# RowDriver4.net
KiCad netlist of a schematic drawn in EAGLE
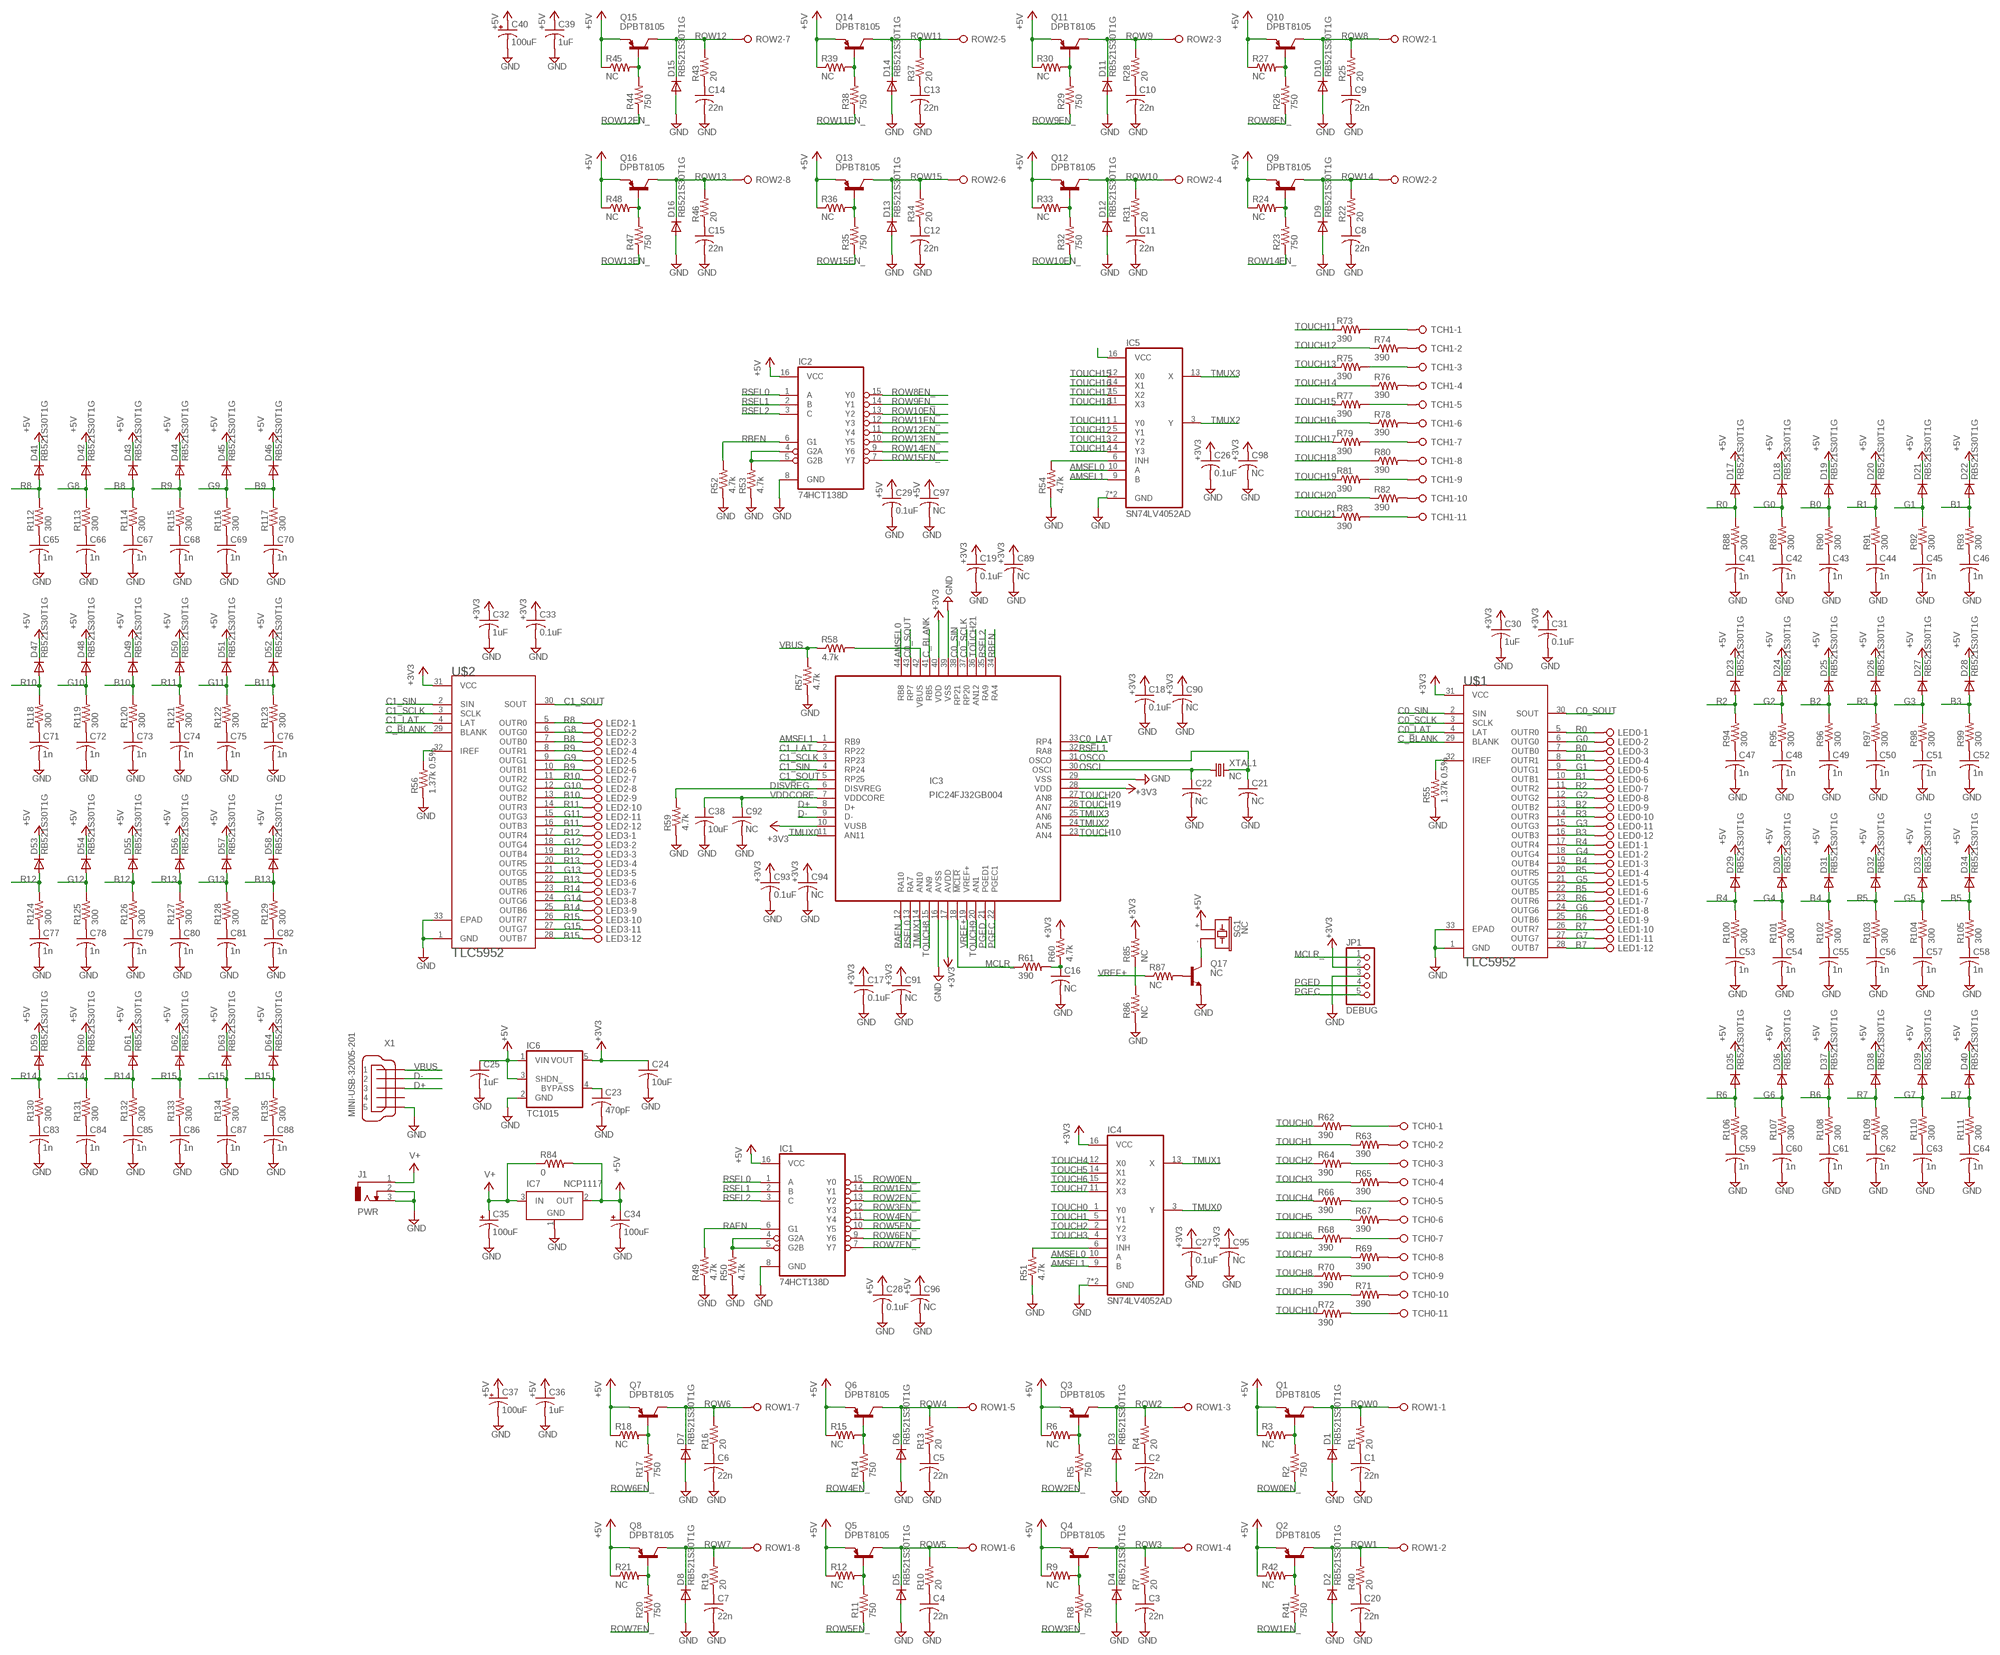
[diagram p0: schematic, sheet 1]

(export (version "E")
  (design (tool "Eeschema 10.0.6"))
  (components
    (comp (ref "C1")
      (value "22n")
      (footprint "eagle-import:C0603")
      (libsource (lib "eagle-import") (part "resistor_C-USC0603"))
    )
    (comp (ref "C2")
      (value "22n")
      (footprint "eagle-import:C0603")
      (libsource (lib "eagle-import") (part "resistor_C-USC0603"))
    )
    (comp (ref "C3")
      (value "22n")
      (footprint "eagle-import:C0603")
      (libsource (lib "eagle-import") (part "resistor_C-USC0603"))
    )
    (comp (ref "C4")
      (value "22n")
      (footprint "eagle-import:C0603")
      (libsource (lib "eagle-import") (part "resistor_C-USC0603"))
    )
    (comp (ref "C5")
      (value "22n")
      (footprint "eagle-import:C0603")
      (libsource (lib "eagle-import") (part "resistor_C-USC0603"))
    )
    (comp (ref "C6")
      (value "22n")
      (footprint "eagle-import:C0603")
      (libsource (lib "eagle-import") (part "resistor_C-USC0603"))
    )
    (comp (ref "C7")
      (value "22n")
      (footprint "eagle-import:C0603")
      (libsource (lib "eagle-import") (part "resistor_C-USC0603"))
    )
    (comp (ref "C8")
      (value "22n")
      (footprint "eagle-import:C0603")
      (libsource (lib "eagle-import") (part "resistor_C-USC0603"))
    )
    (comp (ref "C9")
      (value "22n")
      (footprint "eagle-import:C0603")
      (libsource (lib "eagle-import") (part "resistor_C-USC0603"))
    )
    (comp (ref "C10")
      (value "22n")
      (footprint "eagle-import:C0603")
      (libsource (lib "eagle-import") (part "resistor_C-USC0603"))
    )
    (comp (ref "C11")
      (value "22n")
      (footprint "eagle-import:C0603")
      (libsource (lib "eagle-import") (part "resistor_C-USC0603"))
    )
    (comp (ref "C12")
      (value "22n")
      (footprint "eagle-import:C0603")
      (libsource (lib "eagle-import") (part "resistor_C-USC0603"))
    )
    (comp (ref "C13")
      (value "22n")
      (footprint "eagle-import:C0603")
      (libsource (lib "eagle-import") (part "resistor_C-USC0603"))
    )
    (comp (ref "C14")
      (value "22n")
      (footprint "eagle-import:C0603")
      (libsource (lib "eagle-import") (part "resistor_C-USC0603"))
    )
    (comp (ref "C15")
      (value "22n")
      (footprint "eagle-import:C0603")
      (libsource (lib "eagle-import") (part "resistor_C-USC0603"))
    )
    (comp (ref "C16")
      (value "NC")
      (footprint "eagle-import:C0805")
      (libsource (lib "eagle-import") (part "C-USC0805"))
    )
    (comp (ref "C17")
      (value "0.1uF")
      (footprint "eagle-import:C0805")
      (libsource (lib "eagle-import") (part "C-USC0805"))
    )
    (comp (ref "C18")
      (value "0.1uF")
      (footprint "eagle-import:C0805")
      (libsource (lib "eagle-import") (part "C-USC0805"))
    )
    (comp (ref "C19")
      (value "0.1uF")
      (footprint "eagle-import:C0805")
      (libsource (lib "eagle-import") (part "C-USC0805"))
    )
    (comp (ref "C20")
      (value "22n")
      (footprint "eagle-import:C0603")
      (libsource (lib "eagle-import") (part "resistor_C-USC0603"))
    )
    (comp (ref "C21")
      (value "NC")
      (footprint "eagle-import:C0805")
      (libsource (lib "eagle-import") (part "C-USC0805"))
    )
    (comp (ref "C22")
      (value "NC")
      (footprint "eagle-import:C0805")
      (libsource (lib "eagle-import") (part "C-USC0805"))
    )
    (comp (ref "C23")
      (value "470pF")
      (footprint "eagle-import:C0805")
      (libsource (lib "eagle-import") (part "C-USC0805"))
    )
    (comp (ref "C24")
      (value "10uF")
      (footprint "eagle-import:C1206K")
      (libsource (lib "eagle-import") (part "C-USC1206K"))
    )
    (comp (ref "C25")
      (value "1uF")
      (footprint "eagle-import:C0805")
      (libsource (lib "eagle-import") (part "C-USC0805"))
    )
    (comp (ref "C26")
      (value "0.1uF")
      (footprint "eagle-import:C0805")
      (libsource (lib "eagle-import") (part "C-USC0805"))
    )
    (comp (ref "C27")
      (value "0.1uF")
      (footprint "eagle-import:C0805")
      (libsource (lib "eagle-import") (part "C-USC0805"))
    )
    (comp (ref "C28")
      (value "0.1uF")
      (footprint "eagle-import:C0805")
      (libsource (lib "eagle-import") (part "C-USC0805"))
    )
    (comp (ref "C29")
      (value "0.1uF")
      (footprint "eagle-import:C0805")
      (libsource (lib "eagle-import") (part "C-USC0805"))
    )
    (comp (ref "C30")
      (value "1uF")
      (footprint "eagle-import:C0805")
      (libsource (lib "eagle-import") (part "C-USC0805"))
    )
    (comp (ref "C31")
      (value "0.1uF")
      (footprint "eagle-import:C0805")
      (libsource (lib "eagle-import") (part "C-USC0805"))
    )
    (comp (ref "C32")
      (value "1uF")
      (footprint "eagle-import:C0805")
      (libsource (lib "eagle-import") (part "C-USC0805"))
    )
    (comp (ref "C33")
      (value "0.1uF")
      (footprint "eagle-import:C0805")
      (libsource (lib "eagle-import") (part "C-USC0805"))
    )
    (comp (ref "C34")
      (value "100uF")
      (footprint "eagle-import:PANASONIC_D")
      (libsource (lib "eagle-import") (part "CPOL-USD"))
    )
    (comp (ref "C35")
      (value "100uF")
      (footprint "eagle-import:PANASONIC_D")
      (libsource (lib "eagle-import") (part "CPOL-USD"))
    )
    (comp (ref "C36")
      (value "1uF")
      (footprint "eagle-import:C0805")
      (libsource (lib "eagle-import") (part "C-USC0805"))
    )
    (comp (ref "C37")
      (value "100uF")
      (footprint "eagle-import:PANASONIC_D")
      (libsource (lib "eagle-import") (part "CPOL-USD"))
    )
    (comp (ref "C38")
      (value "10uF")
      (footprint "eagle-import:C1206K")
      (libsource (lib "eagle-import") (part "C-USC1206K"))
    )
    (comp (ref "C39")
      (value "1uF")
      (footprint "eagle-import:C0805")
      (libsource (lib "eagle-import") (part "C-USC0805"))
    )
    (comp (ref "C40")
      (value "100uF")
      (footprint "eagle-import:PANASONIC_D")
      (libsource (lib "eagle-import") (part "CPOL-USD"))
    )
    (comp (ref "C41")
      (value "1n")
      (footprint "eagle-import:C0805")
      (libsource (lib "eagle-import") (part "resistor_C-USC0805"))
    )
    (comp (ref "C42")
      (value "1n")
      (footprint "eagle-import:C0805")
      (libsource (lib "eagle-import") (part "resistor_C-USC0805"))
    )
    (comp (ref "C43")
      (value "1n")
      (footprint "eagle-import:C0805")
      (libsource (lib "eagle-import") (part "resistor_C-USC0805"))
    )
    (comp (ref "C44")
      (value "1n")
      (footprint "eagle-import:C0805")
      (libsource (lib "eagle-import") (part "resistor_C-USC0805"))
    )
    (comp (ref "C45")
      (value "1n")
      (footprint "eagle-import:C0805")
      (libsource (lib "eagle-import") (part "resistor_C-USC0805"))
    )
    (comp (ref "C46")
      (value "1n")
      (footprint "eagle-import:C0805")
      (libsource (lib "eagle-import") (part "resistor_C-USC0805"))
    )
    (comp (ref "C47")
      (value "1n")
      (footprint "eagle-import:C0805")
      (libsource (lib "eagle-import") (part "resistor_C-USC0805"))
    )
    (comp (ref "C48")
      (value "1n")
      (footprint "eagle-import:C0805")
      (libsource (lib "eagle-import") (part "resistor_C-USC0805"))
    )
    (comp (ref "C49")
      (value "1n")
      (footprint "eagle-import:C0805")
      (libsource (lib "eagle-import") (part "resistor_C-USC0805"))
    )
    (comp (ref "C50")
      (value "1n")
      (footprint "eagle-import:C0805")
      (libsource (lib "eagle-import") (part "resistor_C-USC0805"))
    )
    (comp (ref "C51")
      (value "1n")
      (footprint "eagle-import:C0805")
      (libsource (lib "eagle-import") (part "resistor_C-USC0805"))
    )
    (comp (ref "C52")
      (value "1n")
      (footprint "eagle-import:C0805")
      (libsource (lib "eagle-import") (part "resistor_C-USC0805"))
    )
    (comp (ref "C53")
      (value "1n")
      (footprint "eagle-import:C0805")
      (libsource (lib "eagle-import") (part "resistor_C-USC0805"))
    )
    (comp (ref "C54")
      (value "1n")
      (footprint "eagle-import:C0805")
      (libsource (lib "eagle-import") (part "resistor_C-USC0805"))
    )
    (comp (ref "C55")
      (value "1n")
      (footprint "eagle-import:C0805")
      (libsource (lib "eagle-import") (part "resistor_C-USC0805"))
    )
    (comp (ref "C56")
      (value "1n")
      (footprint "eagle-import:C0805")
      (libsource (lib "eagle-import") (part "resistor_C-USC0805"))
    )
    (comp (ref "C57")
      (value "1n")
      (footprint "eagle-import:C0805")
      (libsource (lib "eagle-import") (part "resistor_C-USC0805"))
    )
    (comp (ref "C58")
      (value "1n")
      (footprint "eagle-import:C0805")
      (libsource (lib "eagle-import") (part "resistor_C-USC0805"))
    )
    (comp (ref "C59")
      (value "1n")
      (footprint "eagle-import:C0805")
      (libsource (lib "eagle-import") (part "resistor_C-USC0805"))
    )
    (comp (ref "C60")
      (value "1n")
      (footprint "eagle-import:C0805")
      (libsource (lib "eagle-import") (part "resistor_C-USC0805"))
    )
    (comp (ref "C61")
      (value "1n")
      (footprint "eagle-import:C0805")
      (libsource (lib "eagle-import") (part "resistor_C-USC0805"))
    )
    (comp (ref "C62")
      (value "1n")
      (footprint "eagle-import:C0805")
      (libsource (lib "eagle-import") (part "resistor_C-USC0805"))
    )
    (comp (ref "C63")
      (value "1n")
      (footprint "eagle-import:C0805")
      (libsource (lib "eagle-import") (part "resistor_C-USC0805"))
    )
    (comp (ref "C64")
      (value "1n")
      (footprint "eagle-import:C0805")
      (libsource (lib "eagle-import") (part "resistor_C-USC0805"))
    )
    (comp (ref "C65")
      (value "1n")
      (footprint "eagle-import:C0805")
      (libsource (lib "eagle-import") (part "resistor_C-USC0805"))
    )
    (comp (ref "C66")
      (value "1n")
      (footprint "eagle-import:C0805")
      (libsource (lib "eagle-import") (part "resistor_C-USC0805"))
    )
    (comp (ref "C67")
      (value "1n")
      (footprint "eagle-import:C0805")
      (libsource (lib "eagle-import") (part "resistor_C-USC0805"))
    )
    (comp (ref "C68")
      (value "1n")
      (footprint "eagle-import:C0805")
      (libsource (lib "eagle-import") (part "resistor_C-USC0805"))
    )
    (comp (ref "C69")
      (value "1n")
      (footprint "eagle-import:C0805")
      (libsource (lib "eagle-import") (part "resistor_C-USC0805"))
    )
    (comp (ref "C70")
      (value "1n")
      (footprint "eagle-import:C0805")
      (libsource (lib "eagle-import") (part "resistor_C-USC0805"))
    )
    (comp (ref "C71")
      (value "1n")
      (footprint "eagle-import:C0805")
      (libsource (lib "eagle-import") (part "resistor_C-USC0805"))
    )
    (comp (ref "C72")
      (value "1n")
      (footprint "eagle-import:C0805")
      (libsource (lib "eagle-import") (part "resistor_C-USC0805"))
    )
    (comp (ref "C73")
      (value "1n")
      (footprint "eagle-import:C0805")
      (libsource (lib "eagle-import") (part "resistor_C-USC0805"))
    )
    (comp (ref "C74")
      (value "1n")
      (footprint "eagle-import:C0805")
      (libsource (lib "eagle-import") (part "resistor_C-USC0805"))
    )
    (comp (ref "C75")
      (value "1n")
      (footprint "eagle-import:C0805")
      (libsource (lib "eagle-import") (part "resistor_C-USC0805"))
    )
    (comp (ref "C76")
      (value "1n")
      (footprint "eagle-import:C0805")
      (libsource (lib "eagle-import") (part "resistor_C-USC0805"))
    )
    (comp (ref "C77")
      (value "1n")
      (footprint "eagle-import:C0805")
      (libsource (lib "eagle-import") (part "resistor_C-USC0805"))
    )
    (comp (ref "C78")
      (value "1n")
      (footprint "eagle-import:C0805")
      (libsource (lib "eagle-import") (part "resistor_C-USC0805"))
    )
    (comp (ref "C79")
      (value "1n")
      (footprint "eagle-import:C0805")
      (libsource (lib "eagle-import") (part "resistor_C-USC0805"))
    )
    (comp (ref "C80")
      (value "1n")
      (footprint "eagle-import:C0805")
      (libsource (lib "eagle-import") (part "resistor_C-USC0805"))
    )
    (comp (ref "C81")
      (value "1n")
      (footprint "eagle-import:C0805")
      (libsource (lib "eagle-import") (part "resistor_C-USC0805"))
    )
    (comp (ref "C82")
      (value "1n")
      (footprint "eagle-import:C0805")
      (libsource (lib "eagle-import") (part "resistor_C-USC0805"))
    )
    (comp (ref "C83")
      (value "1n")
      (footprint "eagle-import:C0805")
      (libsource (lib "eagle-import") (part "resistor_C-USC0805"))
    )
    (comp (ref "C84")
      (value "1n")
      (footprint "eagle-import:C0805")
      (libsource (lib "eagle-import") (part "resistor_C-USC0805"))
    )
    (comp (ref "C85")
      (value "1n")
      (footprint "eagle-import:C0805")
      (libsource (lib "eagle-import") (part "resistor_C-USC0805"))
    )
    (comp (ref "C86")
      (value "1n")
      (footprint "eagle-import:C0805")
      (libsource (lib "eagle-import") (part "resistor_C-USC0805"))
    )
    (comp (ref "C87")
      (value "1n")
      (footprint "eagle-import:C0805")
      (libsource (lib "eagle-import") (part "resistor_C-USC0805"))
    )
    (comp (ref "C88")
      (value "1n")
      (footprint "eagle-import:C0805")
      (libsource (lib "eagle-import") (part "resistor_C-USC0805"))
    )
    (comp (ref "C89")
      (value "NC")
      (footprint "eagle-import:C0805")
      (libsource (lib "eagle-import") (part "C-USC0805"))
    )
    (comp (ref "C90")
      (value "NC")
      (footprint "eagle-import:C0805")
      (libsource (lib "eagle-import") (part "C-USC0805"))
    )
    (comp (ref "C91")
      (value "NC")
      (footprint "eagle-import:C0805")
      (libsource (lib "eagle-import") (part "C-USC0805"))
    )
    (comp (ref "C92")
      (value "NC")
      (footprint "eagle-import:C0805")
      (libsource (lib "eagle-import") (part "C-USC0805"))
    )
    (comp (ref "C93")
      (value "0.1uF")
      (footprint "eagle-import:C0805")
      (libsource (lib "eagle-import") (part "C-USC0805"))
    )
    (comp (ref "C94")
      (value "NC")
      (footprint "eagle-import:C0805")
      (libsource (lib "eagle-import") (part "C-USC0805"))
    )
    (comp (ref "C95")
      (value "NC")
      (footprint "eagle-import:C0805")
      (libsource (lib "eagle-import") (part "C-USC0805"))
    )
    (comp (ref "C96")
      (value "NC")
      (footprint "eagle-import:C0805")
      (libsource (lib "eagle-import") (part "C-USC0805"))
    )
    (comp (ref "C97")
      (value "NC")
      (footprint "eagle-import:C0805")
      (libsource (lib "eagle-import") (part "C-USC0805"))
    )
    (comp (ref "C98")
      (value "NC")
      (footprint "eagle-import:C0805")
      (libsource (lib "eagle-import") (part "C-USC0805"))
    )
    (comp (ref "D1")
      (value "RB521S30T1G")
      (footprint "eagle-import:SOD523")
      (libsource (lib "eagle-import") (part "DIODE-SOD523"))
    )
    (comp (ref "D2")
      (value "RB521S30T1G")
      (footprint "eagle-import:SOD523")
      (libsource (lib "eagle-import") (part "DIODE-SOD523"))
    )
    (comp (ref "D3")
      (value "RB521S30T1G")
      (footprint "eagle-import:SOD523")
      (libsource (lib "eagle-import") (part "DIODE-SOD523"))
    )
    (comp (ref "D4")
      (value "RB521S30T1G")
      (footprint "eagle-import:SOD523")
      (libsource (lib "eagle-import") (part "DIODE-SOD523"))
    )
    (comp (ref "D5")
      (value "RB521S30T1G")
      (footprint "eagle-import:SOD523")
      (libsource (lib "eagle-import") (part "DIODE-SOD523"))
    )
    (comp (ref "D6")
      (value "RB521S30T1G")
      (footprint "eagle-import:SOD523")
      (libsource (lib "eagle-import") (part "DIODE-SOD523"))
    )
    (comp (ref "D7")
      (value "RB521S30T1G")
      (footprint "eagle-import:SOD523")
      (libsource (lib "eagle-import") (part "DIODE-SOD523"))
    )
    (comp (ref "D8")
      (value "RB521S30T1G")
      (footprint "eagle-import:SOD523")
      (libsource (lib "eagle-import") (part "DIODE-SOD523"))
    )
    (comp (ref "D9")
      (value "RB521S30T1G")
      (footprint "eagle-import:SOD523")
      (libsource (lib "eagle-import") (part "DIODE-SOD523"))
    )
    (comp (ref "D10")
      (value "RB521S30T1G")
      (footprint "eagle-import:SOD523")
      (libsource (lib "eagle-import") (part "DIODE-SOD523"))
    )
    (comp (ref "D11")
      (value "RB521S30T1G")
      (footprint "eagle-import:SOD523")
      (libsource (lib "eagle-import") (part "DIODE-SOD523"))
    )
    (comp (ref "D12")
      (value "RB521S30T1G")
      (footprint "eagle-import:SOD523")
      (libsource (lib "eagle-import") (part "DIODE-SOD523"))
    )
    (comp (ref "D13")
      (value "RB521S30T1G")
      (footprint "eagle-import:SOD523")
      (libsource (lib "eagle-import") (part "DIODE-SOD523"))
    )
    (comp (ref "D14")
      (value "RB521S30T1G")
      (footprint "eagle-import:SOD523")
      (libsource (lib "eagle-import") (part "DIODE-SOD523"))
    )
    (comp (ref "D15")
      (value "RB521S30T1G")
      (footprint "eagle-import:SOD523")
      (libsource (lib "eagle-import") (part "DIODE-SOD523"))
    )
    (comp (ref "D16")
      (value "RB521S30T1G")
      (footprint "eagle-import:SOD523")
      (libsource (lib "eagle-import") (part "DIODE-SOD523"))
    )
    (comp (ref "D17")
      (value "RB521S30T1G")
      (footprint "eagle-import:SOD523")
      (libsource (lib "eagle-import") (part "DIODE-SOD523"))
    )
    (comp (ref "D18")
      (value "RB521S30T1G")
      (footprint "eagle-import:SOD523")
      (libsource (lib "eagle-import") (part "DIODE-SOD523"))
    )
    (comp (ref "D19")
      (value "RB521S30T1G")
      (footprint "eagle-import:SOD523")
      (libsource (lib "eagle-import") (part "DIODE-SOD523"))
    )
    (comp (ref "D20")
      (value "RB521S30T1G")
      (footprint "eagle-import:SOD523")
      (libsource (lib "eagle-import") (part "DIODE-SOD523"))
    )
    (comp (ref "D21")
      (value "RB521S30T1G")
      (footprint "eagle-import:SOD523")
      (libsource (lib "eagle-import") (part "DIODE-SOD523"))
    )
    (comp (ref "D22")
      (value "RB521S30T1G")
      (footprint "eagle-import:SOD523")
      (libsource (lib "eagle-import") (part "DIODE-SOD523"))
    )
    (comp (ref "D23")
      (value "RB521S30T1G")
      (footprint "eagle-import:SOD523")
      (libsource (lib "eagle-import") (part "DIODE-SOD523"))
    )
    (comp (ref "D24")
      (value "RB521S30T1G")
      (footprint "eagle-import:SOD523")
      (libsource (lib "eagle-import") (part "DIODE-SOD523"))
    )
    (comp (ref "D25")
      (value "RB521S30T1G")
      (footprint "eagle-import:SOD523")
      (libsource (lib "eagle-import") (part "DIODE-SOD523"))
    )
    (comp (ref "D26")
      (value "RB521S30T1G")
      (footprint "eagle-import:SOD523")
      (libsource (lib "eagle-import") (part "DIODE-SOD523"))
    )
    (comp (ref "D27")
      (value "RB521S30T1G")
      (footprint "eagle-import:SOD523")
      (libsource (lib "eagle-import") (part "DIODE-SOD523"))
    )
    (comp (ref "D28")
      (value "RB521S30T1G")
      (footprint "eagle-import:SOD523")
      (libsource (lib "eagle-import") (part "DIODE-SOD523"))
    )
    (comp (ref "D29")
      (value "RB521S30T1G")
      (footprint "eagle-import:SOD523")
      (libsource (lib "eagle-import") (part "DIODE-SOD523"))
    )
    (comp (ref "D30")
      (value "RB521S30T1G")
      (footprint "eagle-import:SOD523")
      (libsource (lib "eagle-import") (part "DIODE-SOD523"))
    )
    (comp (ref "D31")
      (value "RB521S30T1G")
      (footprint "eagle-import:SOD523")
      (libsource (lib "eagle-import") (part "DIODE-SOD523"))
    )
    (comp (ref "D32")
      (value "RB521S30T1G")
      (footprint "eagle-import:SOD523")
      (libsource (lib "eagle-import") (part "DIODE-SOD523"))
    )
    (comp (ref "D33")
      (value "RB521S30T1G")
      (footprint "eagle-import:SOD523")
      (libsource (lib "eagle-import") (part "DIODE-SOD523"))
    )
    (comp (ref "D34")
      (value "RB521S30T1G")
      (footprint "eagle-import:SOD523")
      (libsource (lib "eagle-import") (part "DIODE-SOD523"))
    )
    (comp (ref "D35")
      (value "RB521S30T1G")
      (footprint "eagle-import:SOD523")
      (libsource (lib "eagle-import") (part "DIODE-SOD523"))
    )
    (comp (ref "D36")
      (value "RB521S30T1G")
      (footprint "eagle-import:SOD523")
      (libsource (lib "eagle-import") (part "DIODE-SOD523"))
    )
    (comp (ref "D37")
      (value "RB521S30T1G")
      (footprint "eagle-import:SOD523")
      (libsource (lib "eagle-import") (part "DIODE-SOD523"))
    )
    (comp (ref "D38")
      (value "RB521S30T1G")
      (footprint "eagle-import:SOD523")
      (libsource (lib "eagle-import") (part "DIODE-SOD523"))
    )
    (comp (ref "D39")
      (value "RB521S30T1G")
      (footprint "eagle-import:SOD523")
      (libsource (lib "eagle-import") (part "DIODE-SOD523"))
    )
    (comp (ref "D40")
      (value "RB521S30T1G")
      (footprint "eagle-import:SOD523")
      (libsource (lib "eagle-import") (part "DIODE-SOD523"))
    )
    (comp (ref "D41")
      (value "RB521S30T1G")
      (footprint "eagle-import:SOD523")
      (libsource (lib "eagle-import") (part "DIODE-SOD523"))
    )
    (comp (ref "D42")
      (value "RB521S30T1G")
      (footprint "eagle-import:SOD523")
      (libsource (lib "eagle-import") (part "DIODE-SOD523"))
    )
    (comp (ref "D43")
      (value "RB521S30T1G")
      (footprint "eagle-import:SOD523")
      (libsource (lib "eagle-import") (part "DIODE-SOD523"))
    )
    (comp (ref "D44")
      (value "RB521S30T1G")
      (footprint "eagle-import:SOD523")
      (libsource (lib "eagle-import") (part "DIODE-SOD523"))
    )
    (comp (ref "D45")
      (value "RB521S30T1G")
      (footprint "eagle-import:SOD523")
      (libsource (lib "eagle-import") (part "DIODE-SOD523"))
    )
    (comp (ref "D46")
      (value "RB521S30T1G")
      (footprint "eagle-import:SOD523")
      (libsource (lib "eagle-import") (part "DIODE-SOD523"))
    )
    (comp (ref "D47")
      (value "RB521S30T1G")
      (footprint "eagle-import:SOD523")
      (libsource (lib "eagle-import") (part "DIODE-SOD523"))
    )
    (comp (ref "D48")
      (value "RB521S30T1G")
      (footprint "eagle-import:SOD523")
      (libsource (lib "eagle-import") (part "DIODE-SOD523"))
    )
    (comp (ref "D49")
      (value "RB521S30T1G")
      (footprint "eagle-import:SOD523")
      (libsource (lib "eagle-import") (part "DIODE-SOD523"))
    )
    (comp (ref "D50")
      (value "RB521S30T1G")
      (footprint "eagle-import:SOD523")
      (libsource (lib "eagle-import") (part "DIODE-SOD523"))
    )
    (comp (ref "D51")
      (value "RB521S30T1G")
      (footprint "eagle-import:SOD523")
      (libsource (lib "eagle-import") (part "DIODE-SOD523"))
    )
    (comp (ref "D52")
      (value "RB521S30T1G")
      (footprint "eagle-import:SOD523")
      (libsource (lib "eagle-import") (part "DIODE-SOD523"))
    )
    (comp (ref "D53")
      (value "RB521S30T1G")
      (footprint "eagle-import:SOD523")
      (libsource (lib "eagle-import") (part "DIODE-SOD523"))
    )
    (comp (ref "D54")
      (value "RB521S30T1G")
      (footprint "eagle-import:SOD523")
      (libsource (lib "eagle-import") (part "DIODE-SOD523"))
    )
    (comp (ref "D55")
      (value "RB521S30T1G")
      (footprint "eagle-import:SOD523")
      (libsource (lib "eagle-import") (part "DIODE-SOD523"))
    )
    (comp (ref "D56")
      (value "RB521S30T1G")
      (footprint "eagle-import:SOD523")
      (libsource (lib "eagle-import") (part "DIODE-SOD523"))
    )
    (comp (ref "D57")
      (value "RB521S30T1G")
      (footprint "eagle-import:SOD523")
      (libsource (lib "eagle-import") (part "DIODE-SOD523"))
    )
    (comp (ref "D58")
      (value "RB521S30T1G")
      (footprint "eagle-import:SOD523")
      (libsource (lib "eagle-import") (part "DIODE-SOD523"))
    )
    (comp (ref "D59")
      (value "RB521S30T1G")
      (footprint "eagle-import:SOD523")
      (libsource (lib "eagle-import") (part "DIODE-SOD523"))
    )
    (comp (ref "D60")
      (value "RB521S30T1G")
      (footprint "eagle-import:SOD523")
      (libsource (lib "eagle-import") (part "DIODE-SOD523"))
    )
    (comp (ref "D61")
      (value "RB521S30T1G")
      (footprint "eagle-import:SOD523")
      (libsource (lib "eagle-import") (part "DIODE-SOD523"))
    )
    (comp (ref "D62")
      (value "RB521S30T1G")
      (footprint "eagle-import:SOD523")
      (libsource (lib "eagle-import") (part "DIODE-SOD523"))
    )
    (comp (ref "D63")
      (value "RB521S30T1G")
      (footprint "eagle-import:SOD523")
      (libsource (lib "eagle-import") (part "DIODE-SOD523"))
    )
    (comp (ref "D64")
      (value "RB521S30T1G")
      (footprint "eagle-import:SOD523")
      (libsource (lib "eagle-import") (part "DIODE-SOD523"))
    )
    (comp (ref "IC1")
      (value "74HCT138D")
      (footprint "eagle-import:SO16")
      (libsource (lib "eagle-import") (part "74138DHCT"))
    )
    (comp (ref "IC2")
      (value "74HCT138D")
      (footprint "eagle-import:SO16")
      (libsource (lib "eagle-import") (part "74138DHCT"))
    )
    (comp (ref "IC3")
      (value "PIC24FJ32GB004")
      (footprint "eagle-import:TQFP44")
      (fields (field (name "MPN") "PIC24FJ32GB004-E/PT"))
      (libsource (lib "eagle-import") (part "PIC24FJ32GB004"))
    )
    (comp (ref "IC4")
      (value "SN74LV4052AD")
      (footprint "eagle-import:SO16")
      (libsource (lib "eagle-import") (part "SN74LV4052AD"))
    )
    (comp (ref "IC5")
      (value "SN74LV4052AD")
      (footprint "eagle-import:SO16")
      (libsource (lib "eagle-import") (part "SN74LV4052AD"))
    )
    (comp (ref "IC6")
      (value "TC1015")
      (footprint "eagle-import:SOT23-5L")
      (libsource (lib "eagle-import") (part "TC1015"))
    )
    (comp (ref "IC7")
      (value "NCP1117")
      (footprint "eagle-import:SOT223")
      (libsource (lib "eagle-import") (part "NCP1117"))
    )
    (comp (ref "J1")
      (value "PWR")
      (footprint "eagle-import:DCJ0303")
      (libsource (lib "eagle-import") (part "DCJ0303"))
    )
    (comp (ref "JP1")
      (value "DEBUG")
      (footprint "eagle-import:1X05_90")
      (libsource (lib "eagle-import") (part "PINHD-1X5/90"))
    )
    (comp (ref "LED0")
      (value "OSTVN12A150")
      (footprint "eagle-import:OSTVN12")
      (libsource (lib "eagle-import") (part "OSTVN12A150"))
    )
    (comp (ref "LED1")
      (value "OSTVN12A150")
      (footprint "eagle-import:OSTVN12")
      (libsource (lib "eagle-import") (part "OSTVN12A150"))
    )
    (comp (ref "LED2")
      (value "OSTVN12A150")
      (footprint "eagle-import:OSTVN12")
      (libsource (lib "eagle-import") (part "OSTVN12A150"))
    )
    (comp (ref "LED3")
      (value "OSTVN12A150")
      (footprint "eagle-import:OSTVN12")
      (libsource (lib "eagle-import") (part "OSTVN12A150"))
    )
    (comp (ref "Q1")
      (value "DPBT8105")
      (footprint "eagle-import:SOT23")
      (libsource (lib "eagle-import") (part "DPBT8105"))
    )
    (comp (ref "Q2")
      (value "DPBT8105")
      (footprint "eagle-import:SOT23")
      (libsource (lib "eagle-import") (part "DPBT8105"))
    )
    (comp (ref "Q3")
      (value "DPBT8105")
      (footprint "eagle-import:SOT23")
      (libsource (lib "eagle-import") (part "DPBT8105"))
    )
    (comp (ref "Q4")
      (value "DPBT8105")
      (footprint "eagle-import:SOT23")
      (libsource (lib "eagle-import") (part "DPBT8105"))
    )
    (comp (ref "Q5")
      (value "DPBT8105")
      (footprint "eagle-import:SOT23")
      (libsource (lib "eagle-import") (part "DPBT8105"))
    )
    (comp (ref "Q6")
      (value "DPBT8105")
      (footprint "eagle-import:SOT23")
      (libsource (lib "eagle-import") (part "DPBT8105"))
    )
    (comp (ref "Q7")
      (value "DPBT8105")
      (footprint "eagle-import:SOT23")
      (libsource (lib "eagle-import") (part "DPBT8105"))
    )
    (comp (ref "Q8")
      (value "DPBT8105")
      (footprint "eagle-import:SOT23")
      (libsource (lib "eagle-import") (part "DPBT8105"))
    )
    (comp (ref "Q9")
      (value "DPBT8105")
      (footprint "eagle-import:SOT23")
      (libsource (lib "eagle-import") (part "DPBT8105"))
    )
    (comp (ref "Q10")
      (value "DPBT8105")
      (footprint "eagle-import:SOT23")
      (libsource (lib "eagle-import") (part "DPBT8105"))
    )
    (comp (ref "Q11")
      (value "DPBT8105")
      (footprint "eagle-import:SOT23")
      (libsource (lib "eagle-import") (part "DPBT8105"))
    )
    (comp (ref "Q12")
      (value "DPBT8105")
      (footprint "eagle-import:SOT23")
      (libsource (lib "eagle-import") (part "DPBT8105"))
    )
    (comp (ref "Q13")
      (value "DPBT8105")
      (footprint "eagle-import:SOT23")
      (libsource (lib "eagle-import") (part "DPBT8105"))
    )
    (comp (ref "Q14")
      (value "DPBT8105")
      (footprint "eagle-import:SOT23")
      (libsource (lib "eagle-import") (part "DPBT8105"))
    )
    (comp (ref "Q15")
      (value "DPBT8105")
      (footprint "eagle-import:SOT23")
      (libsource (lib "eagle-import") (part "DPBT8105"))
    )
    (comp (ref "Q16")
      (value "DPBT8105")
      (footprint "eagle-import:SOT23")
      (libsource (lib "eagle-import") (part "DPBT8105"))
    )
    (comp (ref "Q17")
      (value "NC")
      (footprint "eagle-import:SOT23-EBC")
      (libsource (lib "eagle-import") (part "-NPN-SOT23-EBC"))
    )
    (comp (ref "R1")
      (value "20")
      (footprint "eagle-import:R0603")
      (libsource (lib "eagle-import") (part "R-US_R0603"))
    )
    (comp (ref "R2")
      (value "750")
      (footprint "eagle-import:R0603")
      (libsource (lib "eagle-import") (part "R-US_R0603"))
    )
    (comp (ref "R3")
      (value "NC")
      (footprint "eagle-import:R0603")
      (libsource (lib "eagle-import") (part "R-US_R0603"))
    )
    (comp (ref "R4")
      (value "20")
      (footprint "eagle-import:R0603")
      (libsource (lib "eagle-import") (part "R-US_R0603"))
    )
    (comp (ref "R5")
      (value "750")
      (footprint "eagle-import:R0603")
      (libsource (lib "eagle-import") (part "R-US_R0603"))
    )
    (comp (ref "R6")
      (value "NC")
      (footprint "eagle-import:R0603")
      (libsource (lib "eagle-import") (part "R-US_R0603"))
    )
    (comp (ref "R7")
      (value "20")
      (footprint "eagle-import:R0603")
      (libsource (lib "eagle-import") (part "R-US_R0603"))
    )
    (comp (ref "R8")
      (value "750")
      (footprint "eagle-import:R0603")
      (libsource (lib "eagle-import") (part "R-US_R0603"))
    )
    (comp (ref "R9")
      (value "NC")
      (footprint "eagle-import:R0603")
      (libsource (lib "eagle-import") (part "R-US_R0603"))
    )
    (comp (ref "R10")
      (value "20")
      (footprint "eagle-import:R0603")
      (libsource (lib "eagle-import") (part "R-US_R0603"))
    )
    (comp (ref "R11")
      (value "750")
      (footprint "eagle-import:R0603")
      (libsource (lib "eagle-import") (part "R-US_R0603"))
    )
    (comp (ref "R12")
      (value "NC")
      (footprint "eagle-import:R0603")
      (libsource (lib "eagle-import") (part "R-US_R0603"))
    )
    (comp (ref "R13")
      (value "20")
      (footprint "eagle-import:R0603")
      (libsource (lib "eagle-import") (part "R-US_R0603"))
    )
    (comp (ref "R14")
      (value "750")
      (footprint "eagle-import:R0603")
      (libsource (lib "eagle-import") (part "R-US_R0603"))
    )
    (comp (ref "R15")
      (value "NC")
      (footprint "eagle-import:R0603")
      (libsource (lib "eagle-import") (part "R-US_R0603"))
    )
    (comp (ref "R16")
      (value "20")
      (footprint "eagle-import:R0603")
      (libsource (lib "eagle-import") (part "R-US_R0603"))
    )
    (comp (ref "R17")
      (value "750")
      (footprint "eagle-import:R0603")
      (libsource (lib "eagle-import") (part "R-US_R0603"))
    )
    (comp (ref "R18")
      (value "NC")
      (footprint "eagle-import:R0603")
      (libsource (lib "eagle-import") (part "R-US_R0603"))
    )
    (comp (ref "R19")
      (value "20")
      (footprint "eagle-import:R0603")
      (libsource (lib "eagle-import") (part "R-US_R0603"))
    )
    (comp (ref "R20")
      (value "750")
      (footprint "eagle-import:R0603")
      (libsource (lib "eagle-import") (part "R-US_R0603"))
    )
    (comp (ref "R21")
      (value "NC")
      (footprint "eagle-import:R0603")
      (libsource (lib "eagle-import") (part "R-US_R0603"))
    )
    (comp (ref "R22")
      (value "20")
      (footprint "eagle-import:R0603")
      (libsource (lib "eagle-import") (part "R-US_R0603"))
    )
    (comp (ref "R23")
      (value "750")
      (footprint "eagle-import:R0603")
      (libsource (lib "eagle-import") (part "R-US_R0603"))
    )
    (comp (ref "R24")
      (value "NC")
      (footprint "eagle-import:R0603")
      (libsource (lib "eagle-import") (part "R-US_R0603"))
    )
    (comp (ref "R25")
      (value "20")
      (footprint "eagle-import:R0603")
      (libsource (lib "eagle-import") (part "R-US_R0603"))
    )
    (comp (ref "R26")
      (value "750")
      (footprint "eagle-import:R0603")
      (libsource (lib "eagle-import") (part "R-US_R0603"))
    )
    (comp (ref "R27")
      (value "NC")
      (footprint "eagle-import:R0603")
      (libsource (lib "eagle-import") (part "R-US_R0603"))
    )
    (comp (ref "R28")
      (value "20")
      (footprint "eagle-import:R0603")
      (libsource (lib "eagle-import") (part "R-US_R0603"))
    )
    (comp (ref "R29")
      (value "750")
      (footprint "eagle-import:R0603")
      (libsource (lib "eagle-import") (part "R-US_R0603"))
    )
    (comp (ref "R30")
      (value "NC")
      (footprint "eagle-import:R0603")
      (libsource (lib "eagle-import") (part "R-US_R0603"))
    )
    (comp (ref "R31")
      (value "20")
      (footprint "eagle-import:R0603")
      (libsource (lib "eagle-import") (part "R-US_R0603"))
    )
    (comp (ref "R32")
      (value "750")
      (footprint "eagle-import:R0603")
      (libsource (lib "eagle-import") (part "R-US_R0603"))
    )
    (comp (ref "R33")
      (value "NC")
      (footprint "eagle-import:R0603")
      (libsource (lib "eagle-import") (part "R-US_R0603"))
    )
    (comp (ref "R34")
      (value "20")
      (footprint "eagle-import:R0603")
      (libsource (lib "eagle-import") (part "R-US_R0603"))
    )
    (comp (ref "R35")
      (value "750")
      (footprint "eagle-import:R0603")
      (libsource (lib "eagle-import") (part "R-US_R0603"))
    )
    (comp (ref "R36")
      (value "NC")
      (footprint "eagle-import:R0603")
      (libsource (lib "eagle-import") (part "R-US_R0603"))
    )
    (comp (ref "R37")
      (value "20")
      (footprint "eagle-import:R0603")
      (libsource (lib "eagle-import") (part "R-US_R0603"))
    )
    (comp (ref "R38")
      (value "750")
      (footprint "eagle-import:R0603")
      (libsource (lib "eagle-import") (part "R-US_R0603"))
    )
    (comp (ref "R39")
      (value "NC")
      (footprint "eagle-import:R0603")
      (libsource (lib "eagle-import") (part "R-US_R0603"))
    )
    (comp (ref "R40")
      (value "20")
      (footprint "eagle-import:R0603")
      (libsource (lib "eagle-import") (part "R-US_R0603"))
    )
    (comp (ref "R41")
      (value "750")
      (footprint "eagle-import:R0603")
      (libsource (lib "eagle-import") (part "R-US_R0603"))
    )
    (comp (ref "R42")
      (value "NC")
      (footprint "eagle-import:R0603")
      (libsource (lib "eagle-import") (part "R-US_R0603"))
    )
    (comp (ref "R43")
      (value "20")
      (footprint "eagle-import:R0603")
      (libsource (lib "eagle-import") (part "R-US_R0603"))
    )
    (comp (ref "R44")
      (value "750")
      (footprint "eagle-import:R0603")
      (libsource (lib "eagle-import") (part "R-US_R0603"))
    )
    (comp (ref "R45")
      (value "NC")
      (footprint "eagle-import:R0603")
      (libsource (lib "eagle-import") (part "R-US_R0603"))
    )
    (comp (ref "R46")
      (value "20")
      (footprint "eagle-import:R0603")
      (libsource (lib "eagle-import") (part "R-US_R0603"))
    )
    (comp (ref "R47")
      (value "750")
      (footprint "eagle-import:R0603")
      (libsource (lib "eagle-import") (part "R-US_R0603"))
    )
    (comp (ref "R48")
      (value "NC")
      (footprint "eagle-import:R0603")
      (libsource (lib "eagle-import") (part "R-US_R0603"))
    )
    (comp (ref "R49")
      (value "4.7k")
      (footprint "eagle-import:R0805")
      (libsource (lib "eagle-import") (part "R-US_R0805"))
    )
    (comp (ref "R50")
      (value "4.7k")
      (footprint "eagle-import:R0805")
      (libsource (lib "eagle-import") (part "R-US_R0805"))
    )
    (comp (ref "R51")
      (value "4.7k")
      (footprint "eagle-import:R0805")
      (libsource (lib "eagle-import") (part "R-US_R0805"))
    )
    (comp (ref "R52")
      (value "4.7k")
      (footprint "eagle-import:R0805")
      (libsource (lib "eagle-import") (part "R-US_R0805"))
    )
    (comp (ref "R53")
      (value "4.7k")
      (footprint "eagle-import:R0805")
      (libsource (lib "eagle-import") (part "R-US_R0805"))
    )
    (comp (ref "R54")
      (value "4.7k")
      (footprint "eagle-import:R0805")
      (libsource (lib "eagle-import") (part "R-US_R0805"))
    )
    (comp (ref "R55")
      (value "1.37k 0.5%")
      (footprint "eagle-import:R0805")
      (libsource (lib "eagle-import") (part "R-US_R0805"))
    )
    (comp (ref "R56")
      (value "1.37k 0.5%")
      (footprint "eagle-import:R0805")
      (libsource (lib "eagle-import") (part "R-US_R0805"))
    )
    (comp (ref "R57")
      (value "4.7k")
      (footprint "eagle-import:R0805")
      (libsource (lib "eagle-import") (part "R-US_R0805"))
    )
    (comp (ref "R58")
      (value "4.7k")
      (footprint "eagle-import:R0805")
      (libsource (lib "eagle-import") (part "R-US_R0805"))
    )
    (comp (ref "R59")
      (value "4.7k")
      (footprint "eagle-import:R0805")
      (libsource (lib "eagle-import") (part "R-US_R0805"))
    )
    (comp (ref "R60")
      (value "4.7k")
      (footprint "eagle-import:R0805")
      (libsource (lib "eagle-import") (part "R-US_R0805"))
    )
    (comp (ref "R61")
      (value "390")
      (footprint "eagle-import:R0805")
      (libsource (lib "eagle-import") (part "R-US_R0805"))
    )
    (comp (ref "R62")
      (value "390")
      (footprint "eagle-import:R0805")
      (libsource (lib "eagle-import") (part "R-US_R0805"))
    )
    (comp (ref "R63")
      (value "390")
      (footprint "eagle-import:R0805")
      (libsource (lib "eagle-import") (part "R-US_R0805"))
    )
    (comp (ref "R64")
      (value "390")
      (footprint "eagle-import:R0805")
      (libsource (lib "eagle-import") (part "R-US_R0805"))
    )
    (comp (ref "R65")
      (value "390")
      (footprint "eagle-import:R0805")
      (libsource (lib "eagle-import") (part "R-US_R0805"))
    )
    (comp (ref "R66")
      (value "390")
      (footprint "eagle-import:R0805")
      (libsource (lib "eagle-import") (part "R-US_R0805"))
    )
    (comp (ref "R67")
      (value "390")
      (footprint "eagle-import:R0805")
      (libsource (lib "eagle-import") (part "R-US_R0805"))
    )
    (comp (ref "R68")
      (value "390")
      (footprint "eagle-import:R0805")
      (libsource (lib "eagle-import") (part "R-US_R0805"))
    )
    (comp (ref "R69")
      (value "390")
      (footprint "eagle-import:R0805")
      (libsource (lib "eagle-import") (part "R-US_R0805"))
    )
    (comp (ref "R70")
      (value "390")
      (footprint "eagle-import:R0805")
      (libsource (lib "eagle-import") (part "R-US_R0805"))
    )
    (comp (ref "R71")
      (value "390")
      (footprint "eagle-import:R0805")
      (libsource (lib "eagle-import") (part "R-US_R0805"))
    )
    (comp (ref "R72")
      (value "390")
      (footprint "eagle-import:R0805")
      (libsource (lib "eagle-import") (part "R-US_R0805"))
    )
    (comp (ref "R73")
      (value "390")
      (footprint "eagle-import:R0805")
      (libsource (lib "eagle-import") (part "R-US_R0805"))
    )
    (comp (ref "R74")
      (value "390")
      (footprint "eagle-import:R0805")
      (libsource (lib "eagle-import") (part "R-US_R0805"))
    )
    (comp (ref "R75")
      (value "390")
      (footprint "eagle-import:R0805")
      (libsource (lib "eagle-import") (part "R-US_R0805"))
    )
    (comp (ref "R76")
      (value "390")
      (footprint "eagle-import:R0805")
      (libsource (lib "eagle-import") (part "R-US_R0805"))
    )
    (comp (ref "R77")
      (value "390")
      (footprint "eagle-import:R0805")
      (libsource (lib "eagle-import") (part "R-US_R0805"))
    )
    (comp (ref "R78")
      (value "390")
      (footprint "eagle-import:R0805")
      (libsource (lib "eagle-import") (part "R-US_R0805"))
    )
    (comp (ref "R79")
      (value "390")
      (footprint "eagle-import:R0805")
      (libsource (lib "eagle-import") (part "R-US_R0805"))
    )
    (comp (ref "R80")
      (value "390")
      (footprint "eagle-import:R0805")
      (libsource (lib "eagle-import") (part "R-US_R0805"))
    )
    (comp (ref "R81")
      (value "390")
      (footprint "eagle-import:R0805")
      (libsource (lib "eagle-import") (part "R-US_R0805"))
    )
    (comp (ref "R82")
      (value "390")
      (footprint "eagle-import:R0805")
      (libsource (lib "eagle-import") (part "R-US_R0805"))
    )
    (comp (ref "R83")
      (value "390")
      (footprint "eagle-import:R0805")
      (libsource (lib "eagle-import") (part "R-US_R0805"))
    )
    (comp (ref "R84")
      (value "0")
      (footprint "eagle-import:R0805")
      (libsource (lib "eagle-import") (part "R-US_R0805"))
    )
    (comp (ref "R85")
      (value "NC")
      (footprint "eagle-import:R0805")
      (libsource (lib "eagle-import") (part "R-US_R0805"))
    )
    (comp (ref "R86")
      (value "NC")
      (footprint "eagle-import:R0805")
      (libsource (lib "eagle-import") (part "R-US_R0805"))
    )
    (comp (ref "R87")
      (value "NC")
      (footprint "eagle-import:R0805")
      (libsource (lib "eagle-import") (part "R-US_R0805"))
    )
    (comp (ref "R88")
      (value "300")
      (footprint "eagle-import:R0805")
      (libsource (lib "eagle-import") (part "R-US_R0805"))
    )
    (comp (ref "R89")
      (value "300")
      (footprint "eagle-import:R0805")
      (libsource (lib "eagle-import") (part "R-US_R0805"))
    )
    (comp (ref "R90")
      (value "300")
      (footprint "eagle-import:R0805")
      (libsource (lib "eagle-import") (part "R-US_R0805"))
    )
    (comp (ref "R91")
      (value "300")
      (footprint "eagle-import:R0805")
      (libsource (lib "eagle-import") (part "R-US_R0805"))
    )
    (comp (ref "R92")
      (value "300")
      (footprint "eagle-import:R0805")
      (libsource (lib "eagle-import") (part "R-US_R0805"))
    )
    (comp (ref "R93")
      (value "300")
      (footprint "eagle-import:R0805")
      (libsource (lib "eagle-import") (part "R-US_R0805"))
    )
    (comp (ref "R94")
      (value "300")
      (footprint "eagle-import:R0805")
      (libsource (lib "eagle-import") (part "R-US_R0805"))
    )
    (comp (ref "R95")
      (value "300")
      (footprint "eagle-import:R0805")
      (libsource (lib "eagle-import") (part "R-US_R0805"))
    )
    (comp (ref "R96")
      (value "300")
      (footprint "eagle-import:R0805")
      (libsource (lib "eagle-import") (part "R-US_R0805"))
    )
    (comp (ref "R97")
      (value "300")
      (footprint "eagle-import:R0805")
      (libsource (lib "eagle-import") (part "R-US_R0805"))
    )
    (comp (ref "R98")
      (value "300")
      (footprint "eagle-import:R0805")
      (libsource (lib "eagle-import") (part "R-US_R0805"))
    )
    (comp (ref "R99")
      (value "300")
      (footprint "eagle-import:R0805")
      (libsource (lib "eagle-import") (part "R-US_R0805"))
    )
    (comp (ref "R100")
      (value "300")
      (footprint "eagle-import:R0805")
      (libsource (lib "eagle-import") (part "R-US_R0805"))
    )
    (comp (ref "R101")
      (value "300")
      (footprint "eagle-import:R0805")
      (libsource (lib "eagle-import") (part "R-US_R0805"))
    )
    (comp (ref "R102")
      (value "300")
      (footprint "eagle-import:R0805")
      (libsource (lib "eagle-import") (part "R-US_R0805"))
    )
    (comp (ref "R103")
      (value "300")
      (footprint "eagle-import:R0805")
      (libsource (lib "eagle-import") (part "R-US_R0805"))
    )
    (comp (ref "R104")
      (value "300")
      (footprint "eagle-import:R0805")
      (libsource (lib "eagle-import") (part "R-US_R0805"))
    )
    (comp (ref "R105")
      (value "300")
      (footprint "eagle-import:R0805")
      (libsource (lib "eagle-import") (part "R-US_R0805"))
    )
    (comp (ref "R106")
      (value "300")
      (footprint "eagle-import:R0805")
      (libsource (lib "eagle-import") (part "R-US_R0805"))
    )
    (comp (ref "R107")
      (value "300")
      (footprint "eagle-import:R0805")
      (libsource (lib "eagle-import") (part "R-US_R0805"))
    )
    (comp (ref "R108")
      (value "300")
      (footprint "eagle-import:R0805")
      (libsource (lib "eagle-import") (part "R-US_R0805"))
    )
    (comp (ref "R109")
      (value "300")
      (footprint "eagle-import:R0805")
      (libsource (lib "eagle-import") (part "R-US_R0805"))
    )
    (comp (ref "R110")
      (value "300")
      (footprint "eagle-import:R0805")
      (libsource (lib "eagle-import") (part "R-US_R0805"))
    )
    (comp (ref "R111")
      (value "300")
      (footprint "eagle-import:R0805")
      (libsource (lib "eagle-import") (part "R-US_R0805"))
    )
    (comp (ref "R112")
      (value "300")
      (footprint "eagle-import:R0805")
      (libsource (lib "eagle-import") (part "R-US_R0805"))
    )
    (comp (ref "R113")
      (value "300")
      (footprint "eagle-import:R0805")
      (libsource (lib "eagle-import") (part "R-US_R0805"))
    )
    (comp (ref "R114")
      (value "300")
      (footprint "eagle-import:R0805")
      (libsource (lib "eagle-import") (part "R-US_R0805"))
    )
    (comp (ref "R115")
      (value "300")
      (footprint "eagle-import:R0805")
      (libsource (lib "eagle-import") (part "R-US_R0805"))
    )
    (comp (ref "R116")
      (value "300")
      (footprint "eagle-import:R0805")
      (libsource (lib "eagle-import") (part "R-US_R0805"))
    )
    (comp (ref "R117")
      (value "300")
      (footprint "eagle-import:R0805")
      (libsource (lib "eagle-import") (part "R-US_R0805"))
    )
    (comp (ref "R118")
      (value "300")
      (footprint "eagle-import:R0805")
      (libsource (lib "eagle-import") (part "R-US_R0805"))
    )
    (comp (ref "R119")
      (value "300")
      (footprint "eagle-import:R0805")
      (libsource (lib "eagle-import") (part "R-US_R0805"))
    )
    (comp (ref "R120")
      (value "300")
      (footprint "eagle-import:R0805")
      (libsource (lib "eagle-import") (part "R-US_R0805"))
    )
    (comp (ref "R121")
      (value "300")
      (footprint "eagle-import:R0805")
      (libsource (lib "eagle-import") (part "R-US_R0805"))
    )
    (comp (ref "R122")
      (value "300")
      (footprint "eagle-import:R0805")
      (libsource (lib "eagle-import") (part "R-US_R0805"))
    )
    (comp (ref "R123")
      (value "300")
      (footprint "eagle-import:R0805")
      (libsource (lib "eagle-import") (part "R-US_R0805"))
    )
    (comp (ref "R124")
      (value "300")
      (footprint "eagle-import:R0805")
      (libsource (lib "eagle-import") (part "R-US_R0805"))
    )
    (comp (ref "R125")
      (value "300")
      (footprint "eagle-import:R0805")
      (libsource (lib "eagle-import") (part "R-US_R0805"))
    )
    (comp (ref "R126")
      (value "300")
      (footprint "eagle-import:R0805")
      (libsource (lib "eagle-import") (part "R-US_R0805"))
    )
    (comp (ref "R127")
      (value "300")
      (footprint "eagle-import:R0805")
      (libsource (lib "eagle-import") (part "R-US_R0805"))
    )
    (comp (ref "R128")
      (value "300")
      (footprint "eagle-import:R0805")
      (libsource (lib "eagle-import") (part "R-US_R0805"))
    )
    (comp (ref "R129")
      (value "300")
      (footprint "eagle-import:R0805")
      (libsource (lib "eagle-import") (part "R-US_R0805"))
    )
    (comp (ref "R130")
      (value "300")
      (footprint "eagle-import:R0805")
      (libsource (lib "eagle-import") (part "R-US_R0805"))
    )
    (comp (ref "R131")
      (value "300")
      (footprint "eagle-import:R0805")
      (libsource (lib "eagle-import") (part "R-US_R0805"))
    )
    (comp (ref "R132")
      (value "300")
      (footprint "eagle-import:R0805")
      (libsource (lib "eagle-import") (part "R-US_R0805"))
    )
    (comp (ref "R133")
      (value "300")
      (footprint "eagle-import:R0805")
      (libsource (lib "eagle-import") (part "R-US_R0805"))
    )
    (comp (ref "R134")
      (value "300")
      (footprint "eagle-import:R0805")
      (libsource (lib "eagle-import") (part "R-US_R0805"))
    )
    (comp (ref "R135")
      (value "300")
      (footprint "eagle-import:R0805")
      (libsource (lib "eagle-import") (part "R-US_R0805"))
    )
    (comp (ref "ROW1")
      (value "OSTVN08A150")
      (footprint "eagle-import:OSTVN08")
      (libsource (lib "eagle-import") (part "OSTVN08A150"))
    )
    (comp (ref "ROW2")
      (value "OSTVN08A150")
      (footprint "eagle-import:OSTVN08")
      (libsource (lib "eagle-import") (part "OSTVN08A150"))
    )
    (comp (ref "SG1")
      (value "NC")
      (footprint "eagle-import:F_CM04P")
      (libsource (lib "eagle-import") (part "F/CM04P"))
    )
    (comp (ref "TCH0")
      (value "OSTVN11A150")
      (footprint "eagle-import:OSTVN11")
      (libsource (lib "eagle-import") (part "OSTVN11A150"))
    )
    (comp (ref "TCH1")
      (value "OSTVN11A150")
      (footprint "eagle-import:OSTVN11")
      (libsource (lib "eagle-import") (part "OSTVN11A150"))
    )
    (comp (ref "U$1")
      (value "TLC5952")
      (footprint "eagle-import:HTSSOP-32POWERPAD")
      (libsource (lib "eagle-import") (part "TLC5952"))
    )
    (comp (ref "U$2")
      (value "TLC5952")
      (footprint "eagle-import:HTSSOP-32POWERPAD")
      (libsource (lib "eagle-import") (part "TLC5952"))
    )
    (comp (ref "X1")
      (value "MINI-USB-32005-201")
      (footprint "eagle-import:32005-201")
      (libsource (lib "eagle-import") (part "MINI-USB-32005-201"))
    )
    (comp (ref "XTAL1")
      (value "NC")
      (footprint "eagle-import:HC49UP")
      (libsource (lib "eagle-import") (part "CRYSTALHC49UP"))
    )
  )
  (nets
    (net (code "1") (name "+3V3") (class "Default")
      (node (ref "C17") (pin "1") (pinfunction "1_1") (pintype "passive"))
      (node (ref "C18") (pin "1") (pinfunction "1_1") (pintype "passive"))
      (node (ref "C19") (pin "1") (pinfunction "1_1") (pintype "passive"))
      (node (ref "C24") (pin "1") (pinfunction "1_1") (pintype "passive"))
      (node (ref "C26") (pin "1") (pinfunction "1_1") (pintype "passive"))
      (node (ref "C27") (pin "1") (pinfunction "1_1") (pintype "passive"))
      (node (ref "C30") (pin "1") (pinfunction "1_1") (pintype "passive"))
      (node (ref "C31") (pin "1") (pinfunction "1_1") (pintype "passive"))
      (node (ref "C32") (pin "1") (pinfunction "1_1") (pintype "passive"))
      (node (ref "C33") (pin "1") (pinfunction "1_1") (pintype "passive"))
      (node (ref "C89") (pin "1") (pinfunction "1_1") (pintype "passive"))
      (node (ref "C90") (pin "1") (pinfunction "1_1") (pintype "passive"))
      (node (ref "C91") (pin "1") (pinfunction "1_1") (pintype "passive"))
      (node (ref "C93") (pin "1") (pinfunction "1_1") (pintype "passive"))
      (node (ref "C94") (pin "1") (pinfunction "1_1") (pintype "passive"))
      (node (ref "C95") (pin "1") (pinfunction "1_1") (pintype "passive"))
      (node (ref "C98") (pin "1") (pinfunction "1_1") (pintype "passive"))
      (node (ref "IC3") (pin "10") (pinfunction "VUSB_10") (pintype "bidirectional"))
      (node (ref "IC3") (pin "17") (pinfunction "AVDD_17") (pintype "power_in"))
      (node (ref "IC3") (pin "28") (pinfunction "VDD_28") (pintype "power_in"))
      (node (ref "IC3") (pin "40") (pinfunction "VDD_40") (pintype "power_in"))
      (node (ref "IC4") (pin "16") (pinfunction "VCC_16") (pintype "bidirectional"))
      (node (ref "IC5") (pin "16") (pinfunction "VCC_16") (pintype "bidirectional"))
      (node (ref "IC6") (pin "5") (pinfunction "VOUT_5") (pintype "passive"))
      (node (ref "JP1") (pin "2") (pinfunction "2_2") (pintype "passive"))
      (node (ref "R60") (pin "2") (pinfunction "2_2") (pintype "passive"))
      (node (ref "R85") (pin "2") (pinfunction "2_2") (pintype "passive"))
      (node (ref "U$1") (pin "31") (pinfunction "VCC_31") (pintype "power_in"))
      (node (ref "U$2") (pin "31") (pinfunction "VCC_31") (pintype "power_in"))
    )
    (net (code "2") (name "+5V") (class "Default")
      (node (ref "C25") (pin "1") (pinfunction "1_1") (pintype "passive"))
      (node (ref "C28") (pin "1") (pinfunction "1_1") (pintype "passive"))
      (node (ref "C29") (pin "1") (pinfunction "1_1") (pintype "passive"))
      (node (ref "C34") (pin "+") (pinfunction "+_+") (pintype "passive"))
      (node (ref "C36") (pin "1") (pinfunction "1_1") (pintype "passive"))
      (node (ref "C37") (pin "+") (pinfunction "+_+") (pintype "passive"))
      (node (ref "C39") (pin "1") (pinfunction "1_1") (pintype "passive"))
      (node (ref "C40") (pin "+") (pinfunction "+_+") (pintype "passive"))
      (node (ref "C96") (pin "1") (pinfunction "1_1") (pintype "passive"))
      (node (ref "C97") (pin "1") (pinfunction "1_1") (pintype "passive"))
      (node (ref "D17") (pin "C") (pinfunction "C_C") (pintype "passive"))
      (node (ref "D18") (pin "C") (pinfunction "C_C") (pintype "passive"))
      (node (ref "D19") (pin "C") (pinfunction "C_C") (pintype "passive"))
      (node (ref "D20") (pin "C") (pinfunction "C_C") (pintype "passive"))
      (node (ref "D21") (pin "C") (pinfunction "C_C") (pintype "passive"))
      (node (ref "D22") (pin "C") (pinfunction "C_C") (pintype "passive"))
      (node (ref "D23") (pin "C") (pinfunction "C_C") (pintype "passive"))
      (node (ref "D24") (pin "C") (pinfunction "C_C") (pintype "passive"))
      (node (ref "D25") (pin "C") (pinfunction "C_C") (pintype "passive"))
      (node (ref "D26") (pin "C") (pinfunction "C_C") (pintype "passive"))
      (node (ref "D27") (pin "C") (pinfunction "C_C") (pintype "passive"))
      (node (ref "D28") (pin "C") (pinfunction "C_C") (pintype "passive"))
      (node (ref "D29") (pin "C") (pinfunction "C_C") (pintype "passive"))
      (node (ref "D30") (pin "C") (pinfunction "C_C") (pintype "passive"))
      (node (ref "D31") (pin "C") (pinfunction "C_C") (pintype "passive"))
      (node (ref "D32") (pin "C") (pinfunction "C_C") (pintype "passive"))
      (node (ref "D33") (pin "C") (pinfunction "C_C") (pintype "passive"))
      (node (ref "D34") (pin "C") (pinfunction "C_C") (pintype "passive"))
      (node (ref "D35") (pin "C") (pinfunction "C_C") (pintype "passive"))
      (node (ref "D36") (pin "C") (pinfunction "C_C") (pintype "passive"))
      (node (ref "D37") (pin "C") (pinfunction "C_C") (pintype "passive"))
      (node (ref "D38") (pin "C") (pinfunction "C_C") (pintype "passive"))
      (node (ref "D39") (pin "C") (pinfunction "C_C") (pintype "passive"))
      (node (ref "D40") (pin "C") (pinfunction "C_C") (pintype "passive"))
      (node (ref "D41") (pin "C") (pinfunction "C_C") (pintype "passive"))
      (node (ref "D42") (pin "C") (pinfunction "C_C") (pintype "passive"))
      (node (ref "D43") (pin "C") (pinfunction "C_C") (pintype "passive"))
      (node (ref "D44") (pin "C") (pinfunction "C_C") (pintype "passive"))
      (node (ref "D45") (pin "C") (pinfunction "C_C") (pintype "passive"))
      (node (ref "D46") (pin "C") (pinfunction "C_C") (pintype "passive"))
      (node (ref "D47") (pin "C") (pinfunction "C_C") (pintype "passive"))
      (node (ref "D48") (pin "C") (pinfunction "C_C") (pintype "passive"))
      (node (ref "D49") (pin "C") (pinfunction "C_C") (pintype "passive"))
      (node (ref "D50") (pin "C") (pinfunction "C_C") (pintype "passive"))
      (node (ref "D51") (pin "C") (pinfunction "C_C") (pintype "passive"))
      (node (ref "D52") (pin "C") (pinfunction "C_C") (pintype "passive"))
      (node (ref "D53") (pin "C") (pinfunction "C_C") (pintype "passive"))
      (node (ref "D54") (pin "C") (pinfunction "C_C") (pintype "passive"))
      (node (ref "D55") (pin "C") (pinfunction "C_C") (pintype "passive"))
      (node (ref "D56") (pin "C") (pinfunction "C_C") (pintype "passive"))
      (node (ref "D57") (pin "C") (pinfunction "C_C") (pintype "passive"))
      (node (ref "D58") (pin "C") (pinfunction "C_C") (pintype "passive"))
      (node (ref "D59") (pin "C") (pinfunction "C_C") (pintype "passive"))
      (node (ref "D60") (pin "C") (pinfunction "C_C") (pintype "passive"))
      (node (ref "D61") (pin "C") (pinfunction "C_C") (pintype "passive"))
      (node (ref "D62") (pin "C") (pinfunction "C_C") (pintype "passive"))
      (node (ref "D63") (pin "C") (pinfunction "C_C") (pintype "passive"))
      (node (ref "D64") (pin "C") (pinfunction "C_C") (pintype "passive"))
      (node (ref "IC1") (pin "16") (pinfunction "VCC_16") (pintype "bidirectional"))
      (node (ref "IC2") (pin "16") (pinfunction "VCC_16") (pintype "bidirectional"))
      (node (ref "IC6") (pin "1") (pinfunction "VIN_1") (pintype "input"))
      (node (ref "IC6") (pin "3") (pinfunction "SHDN__3") (pintype "input"))
      (node (ref "IC7") (pin "2") (pinfunction "OUT_2") (pintype "output"))
      (node (ref "Q1") (pin "2") (pinfunction "E_2") (pintype "passive"))
      (node (ref "Q10") (pin "2") (pinfunction "E_2") (pintype "passive"))
      (node (ref "Q11") (pin "2") (pinfunction "E_2") (pintype "passive"))
      (node (ref "Q12") (pin "2") (pinfunction "E_2") (pintype "passive"))
      (node (ref "Q13") (pin "2") (pinfunction "E_2") (pintype "passive"))
      (node (ref "Q14") (pin "2") (pinfunction "E_2") (pintype "passive"))
      (node (ref "Q15") (pin "2") (pinfunction "E_2") (pintype "passive"))
      (node (ref "Q16") (pin "2") (pinfunction "E_2") (pintype "passive"))
      (node (ref "Q2") (pin "2") (pinfunction "E_2") (pintype "passive"))
      (node (ref "Q3") (pin "2") (pinfunction "E_2") (pintype "passive"))
      (node (ref "Q4") (pin "2") (pinfunction "E_2") (pintype "passive"))
      (node (ref "Q5") (pin "2") (pinfunction "E_2") (pintype "passive"))
      (node (ref "Q6") (pin "2") (pinfunction "E_2") (pintype "passive"))
      (node (ref "Q7") (pin "2") (pinfunction "E_2") (pintype "passive"))
      (node (ref "Q8") (pin "2") (pinfunction "E_2") (pintype "passive"))
      (node (ref "Q9") (pin "2") (pinfunction "E_2") (pintype "passive"))
      (node (ref "R12") (pin "1") (pinfunction "1_1") (pintype "passive"))
      (node (ref "R15") (pin "1") (pinfunction "1_1") (pintype "passive"))
      (node (ref "R18") (pin "1") (pinfunction "1_1") (pintype "passive"))
      (node (ref "R21") (pin "1") (pinfunction "1_1") (pintype "passive"))
      (node (ref "R24") (pin "1") (pinfunction "1_1") (pintype "passive"))
      (node (ref "R27") (pin "1") (pinfunction "1_1") (pintype "passive"))
      (node (ref "R3") (pin "1") (pinfunction "1_1") (pintype "passive"))
      (node (ref "R30") (pin "1") (pinfunction "1_1") (pintype "passive"))
      (node (ref "R33") (pin "1") (pinfunction "1_1") (pintype "passive"))
      (node (ref "R36") (pin "1") (pinfunction "1_1") (pintype "passive"))
      (node (ref "R39") (pin "1") (pinfunction "1_1") (pintype "passive"))
      (node (ref "R42") (pin "1") (pinfunction "1_1") (pintype "passive"))
      (node (ref "R45") (pin "1") (pinfunction "1_1") (pintype "passive"))
      (node (ref "R48") (pin "1") (pinfunction "1_1") (pintype "passive"))
      (node (ref "R6") (pin "1") (pinfunction "1_1") (pintype "passive"))
      (node (ref "R84") (pin "2") (pinfunction "2_2") (pintype "passive"))
      (node (ref "R9") (pin "1") (pinfunction "1_1") (pintype "passive"))
      (node (ref "SG1") (pin "+") (pinfunction "1_+") (pintype "passive"))
    )
    (net (code "3") (name "/AMSEL0") (class "Default")
      (node (ref "IC3") (pin "44") (pinfunction "RB8_44") (pintype "bidirectional"))
      (node (ref "IC4") (pin "10") (pinfunction "A_10") (pintype "input"))
      (node (ref "IC5") (pin "10") (pinfunction "A_10") (pintype "input"))
    )
    (net (code "4") (name "/AMSEL1") (class "Default")
      (node (ref "IC3") (pin "1") (pinfunction "RB9_1") (pintype "bidirectional"))
      (node (ref "IC4") (pin "9") (pinfunction "B_9") (pintype "input"))
      (node (ref "IC5") (pin "9") (pinfunction "B_9") (pintype "input"))
    )
    (net (code "5") (name "/B0") (class "Default")
      (node (ref "D19") (pin "A") (pinfunction "A_A") (pintype "passive"))
      (node (ref "LED0") (pin "3") (pinfunction "KL_3") (pintype "passive"))
      (node (ref "R90") (pin "2") (pinfunction "2_2") (pintype "passive"))
      (node (ref "U$1") (pin "7") (pinfunction "OUTB0_7") (pintype "output"))
    )
    (net (code "6") (name "/B1") (class "Default")
      (node (ref "D22") (pin "A") (pinfunction "A_A") (pintype "passive"))
      (node (ref "LED0") (pin "6") (pinfunction "KL_6") (pintype "passive"))
      (node (ref "R93") (pin "2") (pinfunction "2_2") (pintype "passive"))
      (node (ref "U$1") (pin "10") (pinfunction "OUTB1_10") (pintype "output"))
    )
    (net (code "7") (name "/B2") (class "Default")
      (node (ref "D25") (pin "A") (pinfunction "A_A") (pintype "passive"))
      (node (ref "LED0") (pin "9") (pinfunction "KL_9") (pintype "passive"))
      (node (ref "R96") (pin "2") (pinfunction "2_2") (pintype "passive"))
      (node (ref "U$1") (pin "13") (pinfunction "OUTB2_13") (pintype "output"))
    )
    (net (code "8") (name "/B3") (class "Default")
      (node (ref "D28") (pin "A") (pinfunction "A_A") (pintype "passive"))
      (node (ref "LED0") (pin "12") (pinfunction "KL_12") (pintype "passive"))
      (node (ref "R99") (pin "2") (pinfunction "2_2") (pintype "passive"))
      (node (ref "U$1") (pin "16") (pinfunction "OUTB3_16") (pintype "output"))
    )
    (net (code "9") (name "/B4") (class "Default")
      (node (ref "D31") (pin "A") (pinfunction "A_A") (pintype "passive"))
      (node (ref "LED1") (pin "3") (pinfunction "KL_3") (pintype "passive"))
      (node (ref "R102") (pin "2") (pinfunction "2_2") (pintype "passive"))
      (node (ref "U$1") (pin "19") (pinfunction "OUTB4_19") (pintype "output"))
    )
    (net (code "10") (name "/B5") (class "Default")
      (node (ref "D34") (pin "A") (pinfunction "A_A") (pintype "passive"))
      (node (ref "LED1") (pin "6") (pinfunction "KL_6") (pintype "passive"))
      (node (ref "R105") (pin "2") (pinfunction "2_2") (pintype "passive"))
      (node (ref "U$1") (pin "22") (pinfunction "OUTB5_22") (pintype "output"))
    )
    (net (code "11") (name "/B6") (class "Default")
      (node (ref "D37") (pin "A") (pinfunction "A_A") (pintype "passive"))
      (node (ref "LED1") (pin "9") (pinfunction "KL_9") (pintype "passive"))
      (node (ref "R108") (pin "2") (pinfunction "2_2") (pintype "passive"))
      (node (ref "U$1") (pin "25") (pinfunction "OUTB6_25") (pintype "output"))
    )
    (net (code "12") (name "/B7") (class "Default")
      (node (ref "D40") (pin "A") (pinfunction "A_A") (pintype "passive"))
      (node (ref "LED1") (pin "12") (pinfunction "KL_12") (pintype "passive"))
      (node (ref "R111") (pin "2") (pinfunction "2_2") (pintype "passive"))
      (node (ref "U$1") (pin "28") (pinfunction "OUTB7_28") (pintype "output"))
    )
    (net (code "13") (name "/B8") (class "Default")
      (node (ref "D43") (pin "A") (pinfunction "A_A") (pintype "passive"))
      (node (ref "LED2") (pin "3") (pinfunction "KL_3") (pintype "passive"))
      (node (ref "R114") (pin "2") (pinfunction "2_2") (pintype "passive"))
      (node (ref "U$2") (pin "7") (pinfunction "OUTB0_7") (pintype "output"))
    )
    (net (code "14") (name "/B9") (class "Default")
      (node (ref "D46") (pin "A") (pinfunction "A_A") (pintype "passive"))
      (node (ref "LED2") (pin "6") (pinfunction "KL_6") (pintype "passive"))
      (node (ref "R117") (pin "2") (pinfunction "2_2") (pintype "passive"))
      (node (ref "U$2") (pin "10") (pinfunction "OUTB1_10") (pintype "output"))
    )
    (net (code "15") (name "/B10") (class "Default")
      (node (ref "D49") (pin "A") (pinfunction "A_A") (pintype "passive"))
      (node (ref "LED2") (pin "9") (pinfunction "KL_9") (pintype "passive"))
      (node (ref "R120") (pin "2") (pinfunction "2_2") (pintype "passive"))
      (node (ref "U$2") (pin "13") (pinfunction "OUTB2_13") (pintype "output"))
    )
    (net (code "16") (name "/B11") (class "Default")
      (node (ref "D52") (pin "A") (pinfunction "A_A") (pintype "passive"))
      (node (ref "LED2") (pin "12") (pinfunction "KL_12") (pintype "passive"))
      (node (ref "R123") (pin "2") (pinfunction "2_2") (pintype "passive"))
      (node (ref "U$2") (pin "16") (pinfunction "OUTB3_16") (pintype "output"))
    )
    (net (code "17") (name "/B12") (class "Default")
      (node (ref "D55") (pin "A") (pinfunction "A_A") (pintype "passive"))
      (node (ref "LED3") (pin "3") (pinfunction "KL_3") (pintype "passive"))
      (node (ref "R126") (pin "2") (pinfunction "2_2") (pintype "passive"))
      (node (ref "U$2") (pin "19") (pinfunction "OUTB4_19") (pintype "output"))
    )
    (net (code "18") (name "/B13") (class "Default")
      (node (ref "D58") (pin "A") (pinfunction "A_A") (pintype "passive"))
      (node (ref "LED3") (pin "6") (pinfunction "KL_6") (pintype "passive"))
      (node (ref "R129") (pin "2") (pinfunction "2_2") (pintype "passive"))
      (node (ref "U$2") (pin "22") (pinfunction "OUTB5_22") (pintype "output"))
    )
    (net (code "19") (name "/B14") (class "Default")
      (node (ref "D61") (pin "A") (pinfunction "A_A") (pintype "passive"))
      (node (ref "LED3") (pin "9") (pinfunction "KL_9") (pintype "passive"))
      (node (ref "R132") (pin "2") (pinfunction "2_2") (pintype "passive"))
      (node (ref "U$2") (pin "25") (pinfunction "OUTB6_25") (pintype "output"))
    )
    (net (code "20") (name "/B15") (class "Default")
      (node (ref "D64") (pin "A") (pinfunction "A_A") (pintype "passive"))
      (node (ref "LED3") (pin "12") (pinfunction "KL_12") (pintype "passive"))
      (node (ref "R135") (pin "2") (pinfunction "2_2") (pintype "passive"))
      (node (ref "U$2") (pin "28") (pinfunction "OUTB7_28") (pintype "output"))
    )
    (net (code "21") (name "/C0_LAT") (class "Default")
      (node (ref "IC3") (pin "33") (pinfunction "RP4_33") (pintype "bidirectional"))
      (node (ref "U$1") (pin "4") (pinfunction "LAT_4") (pintype "input"))
    )
    (net (code "22") (name "/C0_SCLK") (class "Default")
      (node (ref "IC3") (pin "37") (pinfunction "RP20_37") (pintype "bidirectional"))
      (node (ref "U$1") (pin "3") (pinfunction "SCLK_3") (pintype "input"))
    )
    (net (code "23") (name "/C0_SIN") (class "Default")
      (node (ref "IC3") (pin "38") (pinfunction "RP21_38") (pintype "bidirectional"))
      (node (ref "U$1") (pin "2") (pinfunction "SIN_2") (pintype "input"))
    )
    (net (code "24") (name "/C0_SOUT") (class "Default")
      (node (ref "IC3") (pin "43") (pinfunction "RP7_43") (pintype "bidirectional"))
      (node (ref "U$1") (pin "30") (pinfunction "SOUT_30") (pintype "output"))
    )
    (net (code "25") (name "/C1_LAT") (class "Default")
      (node (ref "IC3") (pin "2") (pinfunction "RP22_2") (pintype "bidirectional"))
      (node (ref "U$2") (pin "4") (pinfunction "LAT_4") (pintype "input"))
    )
    (net (code "26") (name "/C1_SCLK") (class "Default")
      (node (ref "IC3") (pin "3") (pinfunction "RP23_3") (pintype "bidirectional"))
      (node (ref "U$2") (pin "3") (pinfunction "SCLK_3") (pintype "input"))
    )
    (net (code "27") (name "/C1_SIN") (class "Default")
      (node (ref "IC3") (pin "4") (pinfunction "RP24_4") (pintype "bidirectional"))
      (node (ref "U$2") (pin "2") (pinfunction "SIN_2") (pintype "input"))
    )
    (net (code "28") (name "/C1_SOUT") (class "Default")
      (node (ref "IC3") (pin "5") (pinfunction "RP25_5") (pintype "bidirectional"))
      (node (ref "U$2") (pin "30") (pinfunction "SOUT_30") (pintype "output"))
    )
    (net (code "29") (name "/C_BLANK") (class "Default")
      (node (ref "IC3") (pin "41") (pinfunction "RB5_41") (pintype "bidirectional"))
      (node (ref "U$1") (pin "29") (pinfunction "BLANK_29") (pintype "input"))
      (node (ref "U$2") (pin "29") (pinfunction "BLANK_29") (pintype "input"))
    )
    (net (code "30") (name "/D+") (class "Default")
      (node (ref "IC3") (pin "8") (pinfunction "D+_8") (pintype "bidirectional"))
      (node (ref "X1") (pin "3") (pinfunction "3_3") (pintype "passive"))
    )
    (net (code "31") (name "/D-") (class "Default")
      (node (ref "IC3") (pin "9") (pinfunction "D-_9") (pintype "bidirectional"))
      (node (ref "X1") (pin "2") (pinfunction "2_2") (pintype "passive"))
    )
    (net (code "32") (name "/DISVREG") (class "Default")
      (node (ref "IC3") (pin "6") (pinfunction "DISVREG_6") (pintype "passive"))
      (node (ref "R59") (pin "2") (pinfunction "2_2") (pintype "passive"))
    )
    (net (code "33") (name "/G0") (class "Default")
      (node (ref "D18") (pin "A") (pinfunction "A_A") (pintype "passive"))
      (node (ref "LED0") (pin "2") (pinfunction "KL_2") (pintype "passive"))
      (node (ref "R89") (pin "2") (pinfunction "2_2") (pintype "passive"))
      (node (ref "U$1") (pin "6") (pinfunction "OUTG0_6") (pintype "output"))
    )
    (net (code "34") (name "/G1") (class "Default")
      (node (ref "D21") (pin "A") (pinfunction "A_A") (pintype "passive"))
      (node (ref "LED0") (pin "5") (pinfunction "KL_5") (pintype "passive"))
      (node (ref "R92") (pin "2") (pinfunction "2_2") (pintype "passive"))
      (node (ref "U$1") (pin "9") (pinfunction "OUTG1_9") (pintype "output"))
    )
    (net (code "35") (name "/G2") (class "Default")
      (node (ref "D24") (pin "A") (pinfunction "A_A") (pintype "passive"))
      (node (ref "LED0") (pin "8") (pinfunction "KL_8") (pintype "passive"))
      (node (ref "R95") (pin "2") (pinfunction "2_2") (pintype "passive"))
      (node (ref "U$1") (pin "12") (pinfunction "OUTG2_12") (pintype "output"))
    )
    (net (code "36") (name "/G3") (class "Default")
      (node (ref "D27") (pin "A") (pinfunction "A_A") (pintype "passive"))
      (node (ref "LED0") (pin "11") (pinfunction "KL_11") (pintype "passive"))
      (node (ref "R98") (pin "2") (pinfunction "2_2") (pintype "passive"))
      (node (ref "U$1") (pin "15") (pinfunction "OUTG3_15") (pintype "output"))
    )
    (net (code "37") (name "/G4") (class "Default")
      (node (ref "D30") (pin "A") (pinfunction "A_A") (pintype "passive"))
      (node (ref "LED1") (pin "2") (pinfunction "KL_2") (pintype "passive"))
      (node (ref "R101") (pin "2") (pinfunction "2_2") (pintype "passive"))
      (node (ref "U$1") (pin "18") (pinfunction "OUTG4_18") (pintype "output"))
    )
    (net (code "38") (name "/G5") (class "Default")
      (node (ref "D33") (pin "A") (pinfunction "A_A") (pintype "passive"))
      (node (ref "LED1") (pin "5") (pinfunction "KL_5") (pintype "passive"))
      (node (ref "R104") (pin "2") (pinfunction "2_2") (pintype "passive"))
      (node (ref "U$1") (pin "21") (pinfunction "OUTG5_21") (pintype "output"))
    )
    (net (code "39") (name "/G6") (class "Default")
      (node (ref "D36") (pin "A") (pinfunction "A_A") (pintype "passive"))
      (node (ref "LED1") (pin "8") (pinfunction "KL_8") (pintype "passive"))
      (node (ref "R107") (pin "2") (pinfunction "2_2") (pintype "passive"))
      (node (ref "U$1") (pin "24") (pinfunction "OUTG6_24") (pintype "output"))
    )
    (net (code "40") (name "/G7") (class "Default")
      (node (ref "D39") (pin "A") (pinfunction "A_A") (pintype "passive"))
      (node (ref "LED1") (pin "11") (pinfunction "KL_11") (pintype "passive"))
      (node (ref "R110") (pin "2") (pinfunction "2_2") (pintype "passive"))
      (node (ref "U$1") (pin "27") (pinfunction "OUTG7_27") (pintype "output"))
    )
    (net (code "41") (name "/G8") (class "Default")
      (node (ref "D42") (pin "A") (pinfunction "A_A") (pintype "passive"))
      (node (ref "LED2") (pin "2") (pinfunction "KL_2") (pintype "passive"))
      (node (ref "R113") (pin "2") (pinfunction "2_2") (pintype "passive"))
      (node (ref "U$2") (pin "6") (pinfunction "OUTG0_6") (pintype "output"))
    )
    (net (code "42") (name "/G9") (class "Default")
      (node (ref "D45") (pin "A") (pinfunction "A_A") (pintype "passive"))
      (node (ref "LED2") (pin "5") (pinfunction "KL_5") (pintype "passive"))
      (node (ref "R116") (pin "2") (pinfunction "2_2") (pintype "passive"))
      (node (ref "U$2") (pin "9") (pinfunction "OUTG1_9") (pintype "output"))
    )
    (net (code "43") (name "/G10") (class "Default")
      (node (ref "D48") (pin "A") (pinfunction "A_A") (pintype "passive"))
      (node (ref "LED2") (pin "8") (pinfunction "KL_8") (pintype "passive"))
      (node (ref "R119") (pin "2") (pinfunction "2_2") (pintype "passive"))
      (node (ref "U$2") (pin "12") (pinfunction "OUTG2_12") (pintype "output"))
    )
    (net (code "44") (name "/G11") (class "Default")
      (node (ref "D51") (pin "A") (pinfunction "A_A") (pintype "passive"))
      (node (ref "LED2") (pin "11") (pinfunction "KL_11") (pintype "passive"))
      (node (ref "R122") (pin "2") (pinfunction "2_2") (pintype "passive"))
      (node (ref "U$2") (pin "15") (pinfunction "OUTG3_15") (pintype "output"))
    )
    (net (code "45") (name "/G12") (class "Default")
      (node (ref "D54") (pin "A") (pinfunction "A_A") (pintype "passive"))
      (node (ref "LED3") (pin "2") (pinfunction "KL_2") (pintype "passive"))
      (node (ref "R125") (pin "2") (pinfunction "2_2") (pintype "passive"))
      (node (ref "U$2") (pin "18") (pinfunction "OUTG4_18") (pintype "output"))
    )
    (net (code "46") (name "/G13") (class "Default")
      (node (ref "D57") (pin "A") (pinfunction "A_A") (pintype "passive"))
      (node (ref "LED3") (pin "5") (pinfunction "KL_5") (pintype "passive"))
      (node (ref "R128") (pin "2") (pinfunction "2_2") (pintype "passive"))
      (node (ref "U$2") (pin "21") (pinfunction "OUTG5_21") (pintype "output"))
    )
    (net (code "47") (name "/G14") (class "Default")
      (node (ref "D60") (pin "A") (pinfunction "A_A") (pintype "passive"))
      (node (ref "LED3") (pin "8") (pinfunction "KL_8") (pintype "passive"))
      (node (ref "R131") (pin "2") (pinfunction "2_2") (pintype "passive"))
      (node (ref "U$2") (pin "24") (pinfunction "OUTG6_24") (pintype "output"))
    )
    (net (code "48") (name "/G15") (class "Default")
      (node (ref "D63") (pin "A") (pinfunction "A_A") (pintype "passive"))
      (node (ref "LED3") (pin "11") (pinfunction "KL_11") (pintype "passive"))
      (node (ref "R134") (pin "2") (pinfunction "2_2") (pintype "passive"))
      (node (ref "U$2") (pin "27") (pinfunction "OUTG7_27") (pintype "output"))
    )
    (net (code "49") (name "/MCLR_") (class "Default")
      (node (ref "IC3") (pin "18") (pinfunction "~{MCLR}_18") (pintype "bidirectional"))
      (node (ref "JP1") (pin "1") (pinfunction "1_1") (pintype "passive"))
      (node (ref "R61") (pin "1") (pinfunction "1_1") (pintype "passive"))
    )
    (net (code "50") (name "/OSCI") (class "Default")
      (node (ref "C22") (pin "1") (pinfunction "1_1") (pintype "passive"))
      (node (ref "IC3") (pin "30") (pinfunction "OSCI_30") (pintype "bidirectional"))
      (node (ref "XTAL1") (pin "1") (pinfunction "1_1") (pintype "passive"))
    )
    (net (code "51") (name "/OSCO") (class "Default")
      (node (ref "C21") (pin "1") (pinfunction "1_1") (pintype "passive"))
      (node (ref "IC3") (pin "31") (pinfunction "OSCO_31") (pintype "bidirectional"))
      (node (ref "XTAL1") (pin "2") (pinfunction "2_2") (pintype "passive"))
    )
    (net (code "52") (name "/PGEC") (class "Default")
      (node (ref "IC3") (pin "22") (pinfunction "PGEC1_22") (pintype "bidirectional"))
      (node (ref "JP1") (pin "5") (pinfunction "5_5") (pintype "passive"))
    )
    (net (code "53") (name "/PGED") (class "Default")
      (node (ref "IC3") (pin "21") (pinfunction "PGED1_21") (pintype "bidirectional"))
      (node (ref "JP1") (pin "4") (pinfunction "4_4") (pintype "passive"))
    )
    (net (code "54") (name "/R0") (class "Default")
      (node (ref "D17") (pin "A") (pinfunction "A_A") (pintype "passive"))
      (node (ref "LED0") (pin "1") (pinfunction "KL_1") (pintype "passive"))
      (node (ref "R88") (pin "2") (pinfunction "2_2") (pintype "passive"))
      (node (ref "U$1") (pin "5") (pinfunction "OUTR0_5") (pintype "output"))
    )
    (net (code "55") (name "/R1") (class "Default")
      (node (ref "D20") (pin "A") (pinfunction "A_A") (pintype "passive"))
      (node (ref "LED0") (pin "4") (pinfunction "KL_4") (pintype "passive"))
      (node (ref "R91") (pin "2") (pinfunction "2_2") (pintype "passive"))
      (node (ref "U$1") (pin "8") (pinfunction "OUTR1_8") (pintype "output"))
    )
    (net (code "56") (name "/R2") (class "Default")
      (node (ref "D23") (pin "A") (pinfunction "A_A") (pintype "passive"))
      (node (ref "LED0") (pin "7") (pinfunction "KL_7") (pintype "passive"))
      (node (ref "R94") (pin "2") (pinfunction "2_2") (pintype "passive"))
      (node (ref "U$1") (pin "11") (pinfunction "OUTR2_11") (pintype "output"))
    )
    (net (code "57") (name "/R3") (class "Default")
      (node (ref "D26") (pin "A") (pinfunction "A_A") (pintype "passive"))
      (node (ref "LED0") (pin "10") (pinfunction "KL_10") (pintype "passive"))
      (node (ref "R97") (pin "2") (pinfunction "2_2") (pintype "passive"))
      (node (ref "U$1") (pin "14") (pinfunction "OUTR3_14") (pintype "output"))
    )
    (net (code "58") (name "/R4") (class "Default")
      (node (ref "D29") (pin "A") (pinfunction "A_A") (pintype "passive"))
      (node (ref "LED1") (pin "1") (pinfunction "KL_1") (pintype "passive"))
      (node (ref "R100") (pin "2") (pinfunction "2_2") (pintype "passive"))
      (node (ref "U$1") (pin "17") (pinfunction "OUTR4_17") (pintype "output"))
    )
    (net (code "59") (name "/R5") (class "Default")
      (node (ref "D32") (pin "A") (pinfunction "A_A") (pintype "passive"))
      (node (ref "LED1") (pin "4") (pinfunction "KL_4") (pintype "passive"))
      (node (ref "R103") (pin "2") (pinfunction "2_2") (pintype "passive"))
      (node (ref "U$1") (pin "20") (pinfunction "OUTR5_20") (pintype "output"))
    )
    (net (code "60") (name "/R6") (class "Default")
      (node (ref "D35") (pin "A") (pinfunction "A_A") (pintype "passive"))
      (node (ref "LED1") (pin "7") (pinfunction "KL_7") (pintype "passive"))
      (node (ref "R106") (pin "2") (pinfunction "2_2") (pintype "passive"))
      (node (ref "U$1") (pin "23") (pinfunction "OUTR6_23") (pintype "output"))
    )
    (net (code "61") (name "/R7") (class "Default")
      (node (ref "D38") (pin "A") (pinfunction "A_A") (pintype "passive"))
      (node (ref "LED1") (pin "10") (pinfunction "KL_10") (pintype "passive"))
      (node (ref "R109") (pin "2") (pinfunction "2_2") (pintype "passive"))
      (node (ref "U$1") (pin "26") (pinfunction "OUTR7_26") (pintype "output"))
    )
    (net (code "62") (name "/R8") (class "Default")
      (node (ref "D41") (pin "A") (pinfunction "A_A") (pintype "passive"))
      (node (ref "LED2") (pin "1") (pinfunction "KL_1") (pintype "passive"))
      (node (ref "R112") (pin "2") (pinfunction "2_2") (pintype "passive"))
      (node (ref "U$2") (pin "5") (pinfunction "OUTR0_5") (pintype "output"))
    )
    (net (code "63") (name "/R9") (class "Default")
      (node (ref "D44") (pin "A") (pinfunction "A_A") (pintype "passive"))
      (node (ref "LED2") (pin "4") (pinfunction "KL_4") (pintype "passive"))
      (node (ref "R115") (pin "2") (pinfunction "2_2") (pintype "passive"))
      (node (ref "U$2") (pin "8") (pinfunction "OUTR1_8") (pintype "output"))
    )
    (net (code "64") (name "/R10") (class "Default")
      (node (ref "D47") (pin "A") (pinfunction "A_A") (pintype "passive"))
      (node (ref "LED2") (pin "7") (pinfunction "KL_7") (pintype "passive"))
      (node (ref "R118") (pin "2") (pinfunction "2_2") (pintype "passive"))
      (node (ref "U$2") (pin "11") (pinfunction "OUTR2_11") (pintype "output"))
    )
    (net (code "65") (name "/R11") (class "Default")
      (node (ref "D50") (pin "A") (pinfunction "A_A") (pintype "passive"))
      (node (ref "LED2") (pin "10") (pinfunction "KL_10") (pintype "passive"))
      (node (ref "R121") (pin "2") (pinfunction "2_2") (pintype "passive"))
      (node (ref "U$2") (pin "14") (pinfunction "OUTR3_14") (pintype "output"))
    )
    (net (code "66") (name "/R12") (class "Default")
      (node (ref "D53") (pin "A") (pinfunction "A_A") (pintype "passive"))
      (node (ref "LED3") (pin "1") (pinfunction "KL_1") (pintype "passive"))
      (node (ref "R124") (pin "2") (pinfunction "2_2") (pintype "passive"))
      (node (ref "U$2") (pin "17") (pinfunction "OUTR4_17") (pintype "output"))
    )
    (net (code "67") (name "/R13") (class "Default")
      (node (ref "D56") (pin "A") (pinfunction "A_A") (pintype "passive"))
      (node (ref "LED3") (pin "4") (pinfunction "KL_4") (pintype "passive"))
      (node (ref "R127") (pin "2") (pinfunction "2_2") (pintype "passive"))
      (node (ref "U$2") (pin "20") (pinfunction "OUTR5_20") (pintype "output"))
    )
    (net (code "68") (name "/R14") (class "Default")
      (node (ref "D59") (pin "A") (pinfunction "A_A") (pintype "passive"))
      (node (ref "LED3") (pin "7") (pinfunction "KL_7") (pintype "passive"))
      (node (ref "R130") (pin "2") (pinfunction "2_2") (pintype "passive"))
      (node (ref "U$2") (pin "23") (pinfunction "OUTR6_23") (pintype "output"))
    )
    (net (code "69") (name "/R15") (class "Default")
      (node (ref "D62") (pin "A") (pinfunction "A_A") (pintype "passive"))
      (node (ref "LED3") (pin "10") (pinfunction "KL_10") (pintype "passive"))
      (node (ref "R133") (pin "2") (pinfunction "2_2") (pintype "passive"))
      (node (ref "U$2") (pin "26") (pinfunction "OUTR7_26") (pintype "output"))
    )
    (net (code "70") (name "/RAEN") (class "Default")
      (node (ref "IC1") (pin "6") (pinfunction "G1_6") (pintype "input"))
      (node (ref "IC3") (pin "12") (pinfunction "RA10_12") (pintype "input"))
      (node (ref "R49") (pin "2") (pinfunction "2_2") (pintype "passive"))
    )
    (net (code "71") (name "/RBEN") (class "Default")
      (node (ref "IC2") (pin "6") (pinfunction "G1_6") (pintype "input"))
      (node (ref "IC3") (pin "34") (pinfunction "RA4_34") (pintype "bidirectional"))
      (node (ref "R52") (pin "2") (pinfunction "2_2") (pintype "passive"))
    )
    (net (code "72") (name "/ROW0") (class "Default")
      (node (ref "D1") (pin "C") (pinfunction "C_C") (pintype "passive"))
      (node (ref "Q1") (pin "3") (pinfunction "C_3") (pintype "passive"))
      (node (ref "R1") (pin "2") (pinfunction "2_2") (pintype "passive"))
      (node (ref "ROW1") (pin "1") (pinfunction "KL_1") (pintype "passive"))
    )
    (net (code "73") (name "/ROW0EN_") (class "Default")
      (node (ref "IC1") (pin "15") (pinfunction "Y0_15") (pintype "output"))
      (node (ref "R2") (pin "1") (pinfunction "1_1") (pintype "passive"))
    )
    (net (code "74") (name "/ROW1") (class "Default")
      (node (ref "D2") (pin "C") (pinfunction "C_C") (pintype "passive"))
      (node (ref "Q2") (pin "3") (pinfunction "C_3") (pintype "passive"))
      (node (ref "R40") (pin "2") (pinfunction "2_2") (pintype "passive"))
      (node (ref "ROW1") (pin "2") (pinfunction "KL_2") (pintype "passive"))
    )
    (net (code "75") (name "/ROW1EN_") (class "Default")
      (node (ref "IC1") (pin "14") (pinfunction "Y1_14") (pintype "output"))
      (node (ref "R41") (pin "1") (pinfunction "1_1") (pintype "passive"))
    )
    (net (code "76") (name "/ROW2") (class "Default")
      (node (ref "D3") (pin "C") (pinfunction "C_C") (pintype "passive"))
      (node (ref "Q3") (pin "3") (pinfunction "C_3") (pintype "passive"))
      (node (ref "R4") (pin "2") (pinfunction "2_2") (pintype "passive"))
      (node (ref "ROW1") (pin "3") (pinfunction "KL_3") (pintype "passive"))
    )
    (net (code "77") (name "/ROW2EN_") (class "Default")
      (node (ref "IC1") (pin "13") (pinfunction "Y2_13") (pintype "output"))
      (node (ref "R5") (pin "1") (pinfunction "1_1") (pintype "passive"))
    )
    (net (code "78") (name "/ROW3") (class "Default")
      (node (ref "D4") (pin "C") (pinfunction "C_C") (pintype "passive"))
      (node (ref "Q4") (pin "3") (pinfunction "C_3") (pintype "passive"))
      (node (ref "R7") (pin "2") (pinfunction "2_2") (pintype "passive"))
      (node (ref "ROW1") (pin "4") (pinfunction "KL_4") (pintype "passive"))
    )
    (net (code "79") (name "/ROW3EN_") (class "Default")
      (node (ref "IC1") (pin "12") (pinfunction "Y3_12") (pintype "output"))
      (node (ref "R8") (pin "1") (pinfunction "1_1") (pintype "passive"))
    )
    (net (code "80") (name "/ROW4") (class "Default")
      (node (ref "D6") (pin "C") (pinfunction "C_C") (pintype "passive"))
      (node (ref "Q6") (pin "3") (pinfunction "C_3") (pintype "passive"))
      (node (ref "R13") (pin "2") (pinfunction "2_2") (pintype "passive"))
      (node (ref "ROW1") (pin "5") (pinfunction "KL_5") (pintype "passive"))
    )
    (net (code "81") (name "/ROW4EN_") (class "Default")
      (node (ref "IC1") (pin "11") (pinfunction "Y4_11") (pintype "output"))
      (node (ref "R14") (pin "1") (pinfunction "1_1") (pintype "passive"))
    )
    (net (code "82") (name "/ROW5") (class "Default")
      (node (ref "D5") (pin "C") (pinfunction "C_C") (pintype "passive"))
      (node (ref "Q5") (pin "3") (pinfunction "C_3") (pintype "passive"))
      (node (ref "R10") (pin "2") (pinfunction "2_2") (pintype "passive"))
      (node (ref "ROW1") (pin "6") (pinfunction "KL_6") (pintype "passive"))
    )
    (net (code "83") (name "/ROW5EN_") (class "Default")
      (node (ref "IC1") (pin "10") (pinfunction "Y5_10") (pintype "output"))
      (node (ref "R11") (pin "1") (pinfunction "1_1") (pintype "passive"))
    )
    (net (code "84") (name "/ROW6") (class "Default")
      (node (ref "D7") (pin "C") (pinfunction "C_C") (pintype "passive"))
      (node (ref "Q7") (pin "3") (pinfunction "C_3") (pintype "passive"))
      (node (ref "R16") (pin "2") (pinfunction "2_2") (pintype "passive"))
      (node (ref "ROW1") (pin "7") (pinfunction "KL_7") (pintype "passive"))
    )
    (net (code "85") (name "/ROW6EN_") (class "Default")
      (node (ref "IC1") (pin "9") (pinfunction "Y6_9") (pintype "output"))
      (node (ref "R17") (pin "1") (pinfunction "1_1") (pintype "passive"))
    )
    (net (code "86") (name "/ROW7") (class "Default")
      (node (ref "D8") (pin "C") (pinfunction "C_C") (pintype "passive"))
      (node (ref "Q8") (pin "3") (pinfunction "C_3") (pintype "passive"))
      (node (ref "R19") (pin "2") (pinfunction "2_2") (pintype "passive"))
      (node (ref "ROW1") (pin "8") (pinfunction "KL_8") (pintype "passive"))
    )
    (net (code "87") (name "/ROW7EN_") (class "Default")
      (node (ref "IC1") (pin "7") (pinfunction "Y7_7") (pintype "output"))
      (node (ref "R20") (pin "1") (pinfunction "1_1") (pintype "passive"))
    )
    (net (code "88") (name "/ROW8") (class "Default")
      (node (ref "D10") (pin "C") (pinfunction "C_C") (pintype "passive"))
      (node (ref "Q10") (pin "3") (pinfunction "C_3") (pintype "passive"))
      (node (ref "R25") (pin "2") (pinfunction "2_2") (pintype "passive"))
      (node (ref "ROW2") (pin "1") (pinfunction "KL_1") (pintype "passive"))
    )
    (net (code "89") (name "/ROW8EN_") (class "Default")
      (node (ref "IC2") (pin "15") (pinfunction "Y0_15") (pintype "output"))
      (node (ref "R26") (pin "1") (pinfunction "1_1") (pintype "passive"))
    )
    (net (code "90") (name "/ROW9") (class "Default")
      (node (ref "D11") (pin "C") (pinfunction "C_C") (pintype "passive"))
      (node (ref "Q11") (pin "3") (pinfunction "C_3") (pintype "passive"))
      (node (ref "R28") (pin "2") (pinfunction "2_2") (pintype "passive"))
      (node (ref "ROW2") (pin "3") (pinfunction "KL_3") (pintype "passive"))
    )
    (net (code "91") (name "/ROW9EN_") (class "Default")
      (node (ref "IC2") (pin "14") (pinfunction "Y1_14") (pintype "output"))
      (node (ref "R29") (pin "1") (pinfunction "1_1") (pintype "passive"))
    )
    (net (code "92") (name "/ROW10") (class "Default")
      (node (ref "D12") (pin "C") (pinfunction "C_C") (pintype "passive"))
      (node (ref "Q12") (pin "3") (pinfunction "C_3") (pintype "passive"))
      (node (ref "R31") (pin "2") (pinfunction "2_2") (pintype "passive"))
      (node (ref "ROW2") (pin "4") (pinfunction "KL_4") (pintype "passive"))
    )
    (net (code "93") (name "/ROW10EN_") (class "Default")
      (node (ref "IC2") (pin "13") (pinfunction "Y2_13") (pintype "output"))
      (node (ref "R32") (pin "1") (pinfunction "1_1") (pintype "passive"))
    )
    (net (code "94") (name "/ROW11") (class "Default")
      (node (ref "D14") (pin "C") (pinfunction "C_C") (pintype "passive"))
      (node (ref "Q14") (pin "3") (pinfunction "C_3") (pintype "passive"))
      (node (ref "R37") (pin "2") (pinfunction "2_2") (pintype "passive"))
      (node (ref "ROW2") (pin "5") (pinfunction "KL_5") (pintype "passive"))
    )
    (net (code "95") (name "/ROW11EN_") (class "Default")
      (node (ref "IC2") (pin "12") (pinfunction "Y3_12") (pintype "output"))
      (node (ref "R38") (pin "1") (pinfunction "1_1") (pintype "passive"))
    )
    (net (code "96") (name "/ROW12") (class "Default")
      (node (ref "D15") (pin "C") (pinfunction "C_C") (pintype "passive"))
      (node (ref "Q15") (pin "3") (pinfunction "C_3") (pintype "passive"))
      (node (ref "R43") (pin "2") (pinfunction "2_2") (pintype "passive"))
      (node (ref "ROW2") (pin "7") (pinfunction "KL_7") (pintype "passive"))
    )
    (net (code "97") (name "/ROW12EN_") (class "Default")
      (node (ref "IC2") (pin "11") (pinfunction "Y4_11") (pintype "output"))
      (node (ref "R44") (pin "1") (pinfunction "1_1") (pintype "passive"))
    )
    (net (code "98") (name "/ROW13") (class "Default")
      (node (ref "D16") (pin "C") (pinfunction "C_C") (pintype "passive"))
      (node (ref "Q16") (pin "3") (pinfunction "C_3") (pintype "passive"))
      (node (ref "R46") (pin "2") (pinfunction "2_2") (pintype "passive"))
      (node (ref "ROW2") (pin "8") (pinfunction "KL_8") (pintype "passive"))
    )
    (net (code "99") (name "/ROW13EN_") (class "Default")
      (node (ref "IC2") (pin "10") (pinfunction "Y5_10") (pintype "output"))
      (node (ref "R47") (pin "1") (pinfunction "1_1") (pintype "passive"))
    )
    (net (code "100") (name "/ROW14") (class "Default")
      (node (ref "D9") (pin "C") (pinfunction "C_C") (pintype "passive"))
      (node (ref "Q9") (pin "3") (pinfunction "C_3") (pintype "passive"))
      (node (ref "R22") (pin "2") (pinfunction "2_2") (pintype "passive"))
      (node (ref "ROW2") (pin "2") (pinfunction "KL_2") (pintype "passive"))
    )
    (net (code "101") (name "/ROW14EN_") (class "Default")
      (node (ref "IC2") (pin "9") (pinfunction "Y6_9") (pintype "output"))
      (node (ref "R23") (pin "1") (pinfunction "1_1") (pintype "passive"))
    )
    (net (code "102") (name "/ROW15") (class "Default")
      (node (ref "D13") (pin "C") (pinfunction "C_C") (pintype "passive"))
      (node (ref "Q13") (pin "3") (pinfunction "C_3") (pintype "passive"))
      (node (ref "R34") (pin "2") (pinfunction "2_2") (pintype "passive"))
      (node (ref "ROW2") (pin "6") (pinfunction "KL_6") (pintype "passive"))
    )
    (net (code "103") (name "/ROW15EN_") (class "Default")
      (node (ref "IC2") (pin "7") (pinfunction "Y7_7") (pintype "output"))
      (node (ref "R35") (pin "1") (pinfunction "1_1") (pintype "passive"))
    )
    (net (code "104") (name "/RSEL0") (class "Default")
      (node (ref "IC1") (pin "1") (pinfunction "A_1") (pintype "input"))
      (node (ref "IC2") (pin "1") (pinfunction "A_1") (pintype "input"))
      (node (ref "IC3") (pin "13") (pinfunction "RA7_13") (pintype "bidirectional"))
    )
    (net (code "105") (name "/RSEL1") (class "Default")
      (node (ref "IC1") (pin "2") (pinfunction "B_2") (pintype "input"))
      (node (ref "IC2") (pin "2") (pinfunction "B_2") (pintype "input"))
      (node (ref "IC3") (pin "32") (pinfunction "RA8_32") (pintype "output"))
    )
    (net (code "106") (name "/RSEL2") (class "Default")
      (node (ref "IC1") (pin "3") (pinfunction "C_3") (pintype "input"))
      (node (ref "IC2") (pin "3") (pinfunction "C_3") (pintype "input"))
      (node (ref "IC3") (pin "35") (pinfunction "RA9_35") (pintype "bidirectional"))
    )
    (net (code "107") (name "/TMUX0") (class "Default")
      (node (ref "IC3") (pin "11") (pinfunction "AN11_11") (pintype "bidirectional"))
      (node (ref "IC4") (pin "3") (pinfunction "Y_3") (pintype "bidirectional"))
    )
    (net (code "108") (name "/TMUX1") (class "Default")
      (node (ref "IC3") (pin "14") (pinfunction "AN10_14") (pintype "bidirectional"))
      (node (ref "IC4") (pin "13") (pinfunction "X_13") (pintype "bidirectional"))
    )
    (net (code "109") (name "/TMUX2") (class "Default")
      (node (ref "IC3") (pin "24") (pinfunction "AN5_24") (pintype "bidirectional"))
      (node (ref "IC5") (pin "3") (pinfunction "Y_3") (pintype "bidirectional"))
    )
    (net (code "110") (name "/TMUX3") (class "Default")
      (node (ref "IC3") (pin "25") (pinfunction "AN6_25") (pintype "bidirectional"))
      (node (ref "IC5") (pin "13") (pinfunction "X_13") (pintype "bidirectional"))
    )
    (net (code "111") (name "/TOUCH0") (class "Default")
      (node (ref "IC4") (pin "1") (pinfunction "Y0_1") (pintype "bidirectional"))
      (node (ref "R62") (pin "1") (pinfunction "1_1") (pintype "passive"))
    )
    (net (code "112") (name "/TOUCH1") (class "Default")
      (node (ref "IC4") (pin "5") (pinfunction "Y1_5") (pintype "bidirectional"))
      (node (ref "R63") (pin "1") (pinfunction "1_1") (pintype "passive"))
    )
    (net (code "113") (name "/TOUCH2") (class "Default")
      (node (ref "IC4") (pin "2") (pinfunction "Y2_2") (pintype "bidirectional"))
      (node (ref "R64") (pin "1") (pinfunction "1_1") (pintype "passive"))
    )
    (net (code "114") (name "/TOUCH3") (class "Default")
      (node (ref "IC4") (pin "4") (pinfunction "Y3_4") (pintype "bidirectional"))
      (node (ref "R65") (pin "1") (pinfunction "1_1") (pintype "passive"))
    )
    (net (code "115") (name "/TOUCH4") (class "Default")
      (node (ref "IC4") (pin "12") (pinfunction "X0_12") (pintype "bidirectional"))
      (node (ref "R66") (pin "1") (pinfunction "1_1") (pintype "passive"))
    )
    (net (code "116") (name "/TOUCH5") (class "Default")
      (node (ref "IC4") (pin "14") (pinfunction "X1_14") (pintype "bidirectional"))
      (node (ref "R67") (pin "1") (pinfunction "1_1") (pintype "passive"))
    )
    (net (code "117") (name "/TOUCH6") (class "Default")
      (node (ref "IC4") (pin "15") (pinfunction "X2_15") (pintype "bidirectional"))
      (node (ref "R68") (pin "1") (pinfunction "1_1") (pintype "passive"))
    )
    (net (code "118") (name "/TOUCH7") (class "Default")
      (node (ref "IC4") (pin "11") (pinfunction "X3_11") (pintype "bidirectional"))
      (node (ref "R69") (pin "1") (pinfunction "1_1") (pintype "passive"))
    )
    (net (code "119") (name "/TOUCH8") (class "Default")
      (node (ref "IC3") (pin "15") (pinfunction "AN9_15") (pintype "bidirectional"))
      (node (ref "R70") (pin "1") (pinfunction "1_1") (pintype "passive"))
    )
    (net (code "120") (name "/TOUCH9") (class "Default")
      (node (ref "IC3") (pin "20") (pinfunction "AN1_20") (pintype "bidirectional"))
      (node (ref "R71") (pin "1") (pinfunction "1_1") (pintype "passive"))
    )
    (net (code "121") (name "/TOUCH10") (class "Default")
      (node (ref "IC3") (pin "23") (pinfunction "AN4_23") (pintype "bidirectional"))
      (node (ref "R72") (pin "1") (pinfunction "1_1") (pintype "passive"))
    )
    (net (code "122") (name "/TOUCH11") (class "Default")
      (node (ref "IC5") (pin "1") (pinfunction "Y0_1") (pintype "bidirectional"))
      (node (ref "R73") (pin "1") (pinfunction "1_1") (pintype "passive"))
    )
    (net (code "123") (name "/TOUCH12") (class "Default")
      (node (ref "IC5") (pin "5") (pinfunction "Y1_5") (pintype "bidirectional"))
      (node (ref "R74") (pin "1") (pinfunction "1_1") (pintype "passive"))
    )
    (net (code "124") (name "/TOUCH13") (class "Default")
      (node (ref "IC5") (pin "2") (pinfunction "Y2_2") (pintype "bidirectional"))
      (node (ref "R75") (pin "1") (pinfunction "1_1") (pintype "passive"))
    )
    (net (code "125") (name "/TOUCH14") (class "Default")
      (node (ref "IC5") (pin "4") (pinfunction "Y3_4") (pintype "bidirectional"))
      (node (ref "R76") (pin "1") (pinfunction "1_1") (pintype "passive"))
    )
    (net (code "126") (name "/TOUCH15") (class "Default")
      (node (ref "IC5") (pin "12") (pinfunction "X0_12") (pintype "bidirectional"))
      (node (ref "R77") (pin "1") (pinfunction "1_1") (pintype "passive"))
    )
    (net (code "127") (name "/TOUCH16") (class "Default")
      (node (ref "IC5") (pin "14") (pinfunction "X1_14") (pintype "bidirectional"))
      (node (ref "R78") (pin "1") (pinfunction "1_1") (pintype "passive"))
    )
    (net (code "128") (name "/TOUCH17") (class "Default")
      (node (ref "IC5") (pin "15") (pinfunction "X2_15") (pintype "bidirectional"))
      (node (ref "R79") (pin "1") (pinfunction "1_1") (pintype "passive"))
    )
    (net (code "129") (name "/TOUCH18") (class "Default")
      (node (ref "IC5") (pin "11") (pinfunction "X3_11") (pintype "bidirectional"))
      (node (ref "R80") (pin "1") (pinfunction "1_1") (pintype "passive"))
    )
    (net (code "130") (name "/TOUCH19") (class "Default")
      (node (ref "IC3") (pin "26") (pinfunction "AN7_26") (pintype "bidirectional"))
      (node (ref "R81") (pin "1") (pinfunction "1_1") (pintype "passive"))
    )
    (net (code "131") (name "/TOUCH20") (class "Default")
      (node (ref "IC3") (pin "27") (pinfunction "AN8_27") (pintype "bidirectional"))
      (node (ref "R82") (pin "1") (pinfunction "1_1") (pintype "passive"))
    )
    (net (code "132") (name "/TOUCH21") (class "Default")
      (node (ref "IC3") (pin "36") (pinfunction "AN12_36") (pintype "bidirectional"))
      (node (ref "R83") (pin "1") (pinfunction "1_1") (pintype "passive"))
    )
    (net (code "133") (name "/VBUS") (class "Default")
      (node (ref "R57") (pin "2") (pinfunction "2_2") (pintype "passive"))
      (node (ref "R58") (pin "1") (pinfunction "1_1") (pintype "passive"))
      (node (ref "X1") (pin "1") (pinfunction "1_1") (pintype "passive"))
    )
    (net (code "134") (name "/VDDCORE") (class "Default")
      (node (ref "C38") (pin "1") (pinfunction "1_1") (pintype "passive"))
      (node (ref "C92") (pin "1") (pinfunction "1_1") (pintype "passive"))
      (node (ref "IC3") (pin "7") (pinfunction "VDDCORE_7") (pintype "power_in"))
    )
    (net (code "135") (name "/VREF+") (class "Default")
      (node (ref "IC3") (pin "19") (pinfunction "VREF+_19") (pintype "bidirectional"))
      (node (ref "R87") (pin "1") (pinfunction "1_1") (pintype "passive"))
    )
    (net (code "136") (name "GND") (class "Default")
      (node (ref "C1") (pin "2") (pinfunction "2_2") (pintype "passive"))
      (node (ref "C10") (pin "2") (pinfunction "2_2") (pintype "passive"))
      (node (ref "C11") (pin "2") (pinfunction "2_2") (pintype "passive"))
      (node (ref "C12") (pin "2") (pinfunction "2_2") (pintype "passive"))
      (node (ref "C13") (pin "2") (pinfunction "2_2") (pintype "passive"))
      (node (ref "C14") (pin "2") (pinfunction "2_2") (pintype "passive"))
      (node (ref "C15") (pin "2") (pinfunction "2_2") (pintype "passive"))
      (node (ref "C16") (pin "2") (pinfunction "2_2") (pintype "passive"))
      (node (ref "C17") (pin "2") (pinfunction "2_2") (pintype "passive"))
      (node (ref "C18") (pin "2") (pinfunction "2_2") (pintype "passive"))
      (node (ref "C19") (pin "2") (pinfunction "2_2") (pintype "passive"))
      (node (ref "C2") (pin "2") (pinfunction "2_2") (pintype "passive"))
      (node (ref "C20") (pin "2") (pinfunction "2_2") (pintype "passive"))
      (node (ref "C21") (pin "2") (pinfunction "2_2") (pintype "passive"))
      (node (ref "C22") (pin "2") (pinfunction "2_2") (pintype "passive"))
      (node (ref "C23") (pin "2") (pinfunction "2_2") (pintype "passive"))
      (node (ref "C24") (pin "2") (pinfunction "2_2") (pintype "passive"))
      (node (ref "C25") (pin "2") (pinfunction "2_2") (pintype "passive"))
      (node (ref "C26") (pin "2") (pinfunction "2_2") (pintype "passive"))
      (node (ref "C27") (pin "2") (pinfunction "2_2") (pintype "passive"))
      (node (ref "C28") (pin "2") (pinfunction "2_2") (pintype "passive"))
      (node (ref "C29") (pin "2") (pinfunction "2_2") (pintype "passive"))
      (node (ref "C3") (pin "2") (pinfunction "2_2") (pintype "passive"))
      (node (ref "C30") (pin "2") (pinfunction "2_2") (pintype "passive"))
      (node (ref "C31") (pin "2") (pinfunction "2_2") (pintype "passive"))
      (node (ref "C32") (pin "2") (pinfunction "2_2") (pintype "passive"))
      (node (ref "C33") (pin "2") (pinfunction "2_2") (pintype "passive"))
      (node (ref "C34") (pin "-") (pinfunction "-_-") (pintype "passive"))
      (node (ref "C35") (pin "-") (pinfunction "-_-") (pintype "passive"))
      (node (ref "C36") (pin "2") (pinfunction "2_2") (pintype "passive"))
      (node (ref "C37") (pin "-") (pinfunction "-_-") (pintype "passive"))
      (node (ref "C38") (pin "2") (pinfunction "2_2") (pintype "passive"))
      (node (ref "C39") (pin "2") (pinfunction "2_2") (pintype "passive"))
      (node (ref "C4") (pin "2") (pinfunction "2_2") (pintype "passive"))
      (node (ref "C40") (pin "-") (pinfunction "-_-") (pintype "passive"))
      (node (ref "C41") (pin "2") (pinfunction "2_2") (pintype "passive"))
      (node (ref "C42") (pin "2") (pinfunction "2_2") (pintype "passive"))
      (node (ref "C43") (pin "2") (pinfunction "2_2") (pintype "passive"))
      (node (ref "C44") (pin "2") (pinfunction "2_2") (pintype "passive"))
      (node (ref "C45") (pin "2") (pinfunction "2_2") (pintype "passive"))
      (node (ref "C46") (pin "2") (pinfunction "2_2") (pintype "passive"))
      (node (ref "C47") (pin "2") (pinfunction "2_2") (pintype "passive"))
      (node (ref "C48") (pin "2") (pinfunction "2_2") (pintype "passive"))
      (node (ref "C49") (pin "2") (pinfunction "2_2") (pintype "passive"))
      (node (ref "C5") (pin "2") (pinfunction "2_2") (pintype "passive"))
      (node (ref "C50") (pin "2") (pinfunction "2_2") (pintype "passive"))
      (node (ref "C51") (pin "2") (pinfunction "2_2") (pintype "passive"))
      (node (ref "C52") (pin "2") (pinfunction "2_2") (pintype "passive"))
      (node (ref "C53") (pin "2") (pinfunction "2_2") (pintype "passive"))
      (node (ref "C54") (pin "2") (pinfunction "2_2") (pintype "passive"))
      (node (ref "C55") (pin "2") (pinfunction "2_2") (pintype "passive"))
      (node (ref "C56") (pin "2") (pinfunction "2_2") (pintype "passive"))
      (node (ref "C57") (pin "2") (pinfunction "2_2") (pintype "passive"))
      (node (ref "C58") (pin "2") (pinfunction "2_2") (pintype "passive"))
      (node (ref "C59") (pin "2") (pinfunction "2_2") (pintype "passive"))
      (node (ref "C6") (pin "2") (pinfunction "2_2") (pintype "passive"))
      (node (ref "C60") (pin "2") (pinfunction "2_2") (pintype "passive"))
      (node (ref "C61") (pin "2") (pinfunction "2_2") (pintype "passive"))
      (node (ref "C62") (pin "2") (pinfunction "2_2") (pintype "passive"))
      (node (ref "C63") (pin "2") (pinfunction "2_2") (pintype "passive"))
      (node (ref "C64") (pin "2") (pinfunction "2_2") (pintype "passive"))
      (node (ref "C65") (pin "2") (pinfunction "2_2") (pintype "passive"))
      (node (ref "C66") (pin "2") (pinfunction "2_2") (pintype "passive"))
      (node (ref "C67") (pin "2") (pinfunction "2_2") (pintype "passive"))
      (node (ref "C68") (pin "2") (pinfunction "2_2") (pintype "passive"))
      (node (ref "C69") (pin "2") (pinfunction "2_2") (pintype "passive"))
      (node (ref "C7") (pin "2") (pinfunction "2_2") (pintype "passive"))
      (node (ref "C70") (pin "2") (pinfunction "2_2") (pintype "passive"))
      (node (ref "C71") (pin "2") (pinfunction "2_2") (pintype "passive"))
      (node (ref "C72") (pin "2") (pinfunction "2_2") (pintype "passive"))
      (node (ref "C73") (pin "2") (pinfunction "2_2") (pintype "passive"))
      (node (ref "C74") (pin "2") (pinfunction "2_2") (pintype "passive"))
      (node (ref "C75") (pin "2") (pinfunction "2_2") (pintype "passive"))
      (node (ref "C76") (pin "2") (pinfunction "2_2") (pintype "passive"))
      (node (ref "C77") (pin "2") (pinfunction "2_2") (pintype "passive"))
      (node (ref "C78") (pin "2") (pinfunction "2_2") (pintype "passive"))
      (node (ref "C79") (pin "2") (pinfunction "2_2") (pintype "passive"))
      (node (ref "C8") (pin "2") (pinfunction "2_2") (pintype "passive"))
      (node (ref "C80") (pin "2") (pinfunction "2_2") (pintype "passive"))
      (node (ref "C81") (pin "2") (pinfunction "2_2") (pintype "passive"))
      (node (ref "C82") (pin "2") (pinfunction "2_2") (pintype "passive"))
      (node (ref "C83") (pin "2") (pinfunction "2_2") (pintype "passive"))
      (node (ref "C84") (pin "2") (pinfunction "2_2") (pintype "passive"))
      (node (ref "C85") (pin "2") (pinfunction "2_2") (pintype "passive"))
      (node (ref "C86") (pin "2") (pinfunction "2_2") (pintype "passive"))
      (node (ref "C87") (pin "2") (pinfunction "2_2") (pintype "passive"))
      (node (ref "C88") (pin "2") (pinfunction "2_2") (pintype "passive"))
      (node (ref "C89") (pin "2") (pinfunction "2_2") (pintype "passive"))
      (node (ref "C9") (pin "2") (pinfunction "2_2") (pintype "passive"))
      (node (ref "C90") (pin "2") (pinfunction "2_2") (pintype "passive"))
      (node (ref "C91") (pin "2") (pinfunction "2_2") (pintype "passive"))
      (node (ref "C92") (pin "2") (pinfunction "2_2") (pintype "passive"))
      (node (ref "C93") (pin "2") (pinfunction "2_2") (pintype "passive"))
      (node (ref "C94") (pin "2") (pinfunction "2_2") (pintype "passive"))
      (node (ref "C95") (pin "2") (pinfunction "2_2") (pintype "passive"))
      (node (ref "C96") (pin "2") (pinfunction "2_2") (pintype "passive"))
      (node (ref "C97") (pin "2") (pinfunction "2_2") (pintype "passive"))
      (node (ref "C98") (pin "2") (pinfunction "2_2") (pintype "passive"))
      (node (ref "D1") (pin "A") (pinfunction "A_A") (pintype "passive"))
      (node (ref "D10") (pin "A") (pinfunction "A_A") (pintype "passive"))
      (node (ref "D11") (pin "A") (pinfunction "A_A") (pintype "passive"))
      (node (ref "D12") (pin "A") (pinfunction "A_A") (pintype "passive"))
      (node (ref "D13") (pin "A") (pinfunction "A_A") (pintype "passive"))
      (node (ref "D14") (pin "A") (pinfunction "A_A") (pintype "passive"))
      (node (ref "D15") (pin "A") (pinfunction "A_A") (pintype "passive"))
      (node (ref "D16") (pin "A") (pinfunction "A_A") (pintype "passive"))
      (node (ref "D2") (pin "A") (pinfunction "A_A") (pintype "passive"))
      (node (ref "D3") (pin "A") (pinfunction "A_A") (pintype "passive"))
      (node (ref "D4") (pin "A") (pinfunction "A_A") (pintype "passive"))
      (node (ref "D5") (pin "A") (pinfunction "A_A") (pintype "passive"))
      (node (ref "D6") (pin "A") (pinfunction "A_A") (pintype "passive"))
      (node (ref "D7") (pin "A") (pinfunction "A_A") (pintype "passive"))
      (node (ref "D8") (pin "A") (pinfunction "A_A") (pintype "passive"))
      (node (ref "D9") (pin "A") (pinfunction "A_A") (pintype "passive"))
      (node (ref "IC1") (pin "8") (pinfunction "GND_8") (pintype "bidirectional"))
      (node (ref "IC2") (pin "8") (pinfunction "GND_8") (pintype "bidirectional"))
      (node (ref "IC3") (pin "16") (pinfunction "AVSS_16") (pintype "power_in"))
      (node (ref "IC3") (pin "29") (pinfunction "VSS_29") (pintype "power_in"))
      (node (ref "IC3") (pin "39") (pinfunction "VSS_39") (pintype "power_in"))
      (node (ref "IC4") (pin "7") (pinfunction "GND_7") (pintype "bidirectional"))
      (node (ref "IC4") (pin "8") (pinfunction "GND_8") (pintype "bidirectional"))
      (node (ref "IC5") (pin "7") (pinfunction "GND_7") (pintype "bidirectional"))
      (node (ref "IC5") (pin "8") (pinfunction "GND_8") (pintype "bidirectional"))
      (node (ref "IC6") (pin "2") (pinfunction "GND_2") (pintype "passive"))
      (node (ref "IC7") (pin "1") (pinfunction "GND_1") (pintype "power_in"))
      (node (ref "J1") (pin "2") (pinfunction "2_2") (pintype "passive"))
      (node (ref "J1") (pin "3") (pinfunction "3_3") (pintype "passive"))
      (node (ref "JP1") (pin "3") (pinfunction "3_3") (pintype "passive"))
      (node (ref "Q17") (pin "E") (pinfunction "E_E") (pintype "passive"))
      (node (ref "R49") (pin "1") (pinfunction "1_1") (pintype "passive"))
      (node (ref "R50") (pin "1") (pinfunction "1_1") (pintype "passive"))
      (node (ref "R51") (pin "1") (pinfunction "1_1") (pintype "passive"))
      (node (ref "R52") (pin "1") (pinfunction "1_1") (pintype "passive"))
      (node (ref "R53") (pin "1") (pinfunction "1_1") (pintype "passive"))
      (node (ref "R54") (pin "1") (pinfunction "1_1") (pintype "passive"))
      (node (ref "R55") (pin "1") (pinfunction "1_1") (pintype "passive"))
      (node (ref "R56") (pin "1") (pinfunction "1_1") (pintype "passive"))
      (node (ref "R57") (pin "1") (pinfunction "1_1") (pintype "passive"))
      (node (ref "R59") (pin "1") (pinfunction "1_1") (pintype "passive"))
      (node (ref "R86") (pin "1") (pinfunction "1_1") (pintype "passive"))
      (node (ref "U$1") (pin "1") (pinfunction "GND_1") (pintype "power_in"))
      (node (ref "U$1") (pin "33") (pinfunction "EPAD_33") (pintype "bidirectional"))
      (node (ref "U$2") (pin "1") (pinfunction "GND_1") (pintype "power_in"))
      (node (ref "U$2") (pin "33") (pinfunction "EPAD_33") (pintype "bidirectional"))
      (node (ref "X1") (pin "5") (pinfunction "5_5") (pintype "passive"))
    )
    (net (code "137") (name "Net-(C1-Pad1)") (class "Default")
      (node (ref "C1") (pin "1") (pinfunction "1_1") (pintype "passive"))
      (node (ref "R1") (pin "1") (pinfunction "1_1") (pintype "passive"))
    )
    (net (code "138") (name "Net-(C2-Pad1)") (class "Default")
      (node (ref "C2") (pin "1") (pinfunction "1_1") (pintype "passive"))
      (node (ref "R4") (pin "1") (pinfunction "1_1") (pintype "passive"))
    )
    (net (code "139") (name "Net-(C3-Pad1)") (class "Default")
      (node (ref "C3") (pin "1") (pinfunction "1_1") (pintype "passive"))
      (node (ref "R7") (pin "1") (pinfunction "1_1") (pintype "passive"))
    )
    (net (code "140") (name "Net-(C4-Pad1)") (class "Default")
      (node (ref "C4") (pin "1") (pinfunction "1_1") (pintype "passive"))
      (node (ref "R10") (pin "1") (pinfunction "1_1") (pintype "passive"))
    )
    (net (code "141") (name "Net-(C5-Pad1)") (class "Default")
      (node (ref "C5") (pin "1") (pinfunction "1_1") (pintype "passive"))
      (node (ref "R13") (pin "1") (pinfunction "1_1") (pintype "passive"))
    )
    (net (code "142") (name "Net-(C6-Pad1)") (class "Default")
      (node (ref "C6") (pin "1") (pinfunction "1_1") (pintype "passive"))
      (node (ref "R16") (pin "1") (pinfunction "1_1") (pintype "passive"))
    )
    (net (code "143") (name "Net-(C7-Pad1)") (class "Default")
      (node (ref "C7") (pin "1") (pinfunction "1_1") (pintype "passive"))
      (node (ref "R19") (pin "1") (pinfunction "1_1") (pintype "passive"))
    )
    (net (code "144") (name "Net-(C8-Pad1)") (class "Default")
      (node (ref "C8") (pin "1") (pinfunction "1_1") (pintype "passive"))
      (node (ref "R22") (pin "1") (pinfunction "1_1") (pintype "passive"))
    )
    (net (code "145") (name "Net-(C9-Pad1)") (class "Default")
      (node (ref "C9") (pin "1") (pinfunction "1_1") (pintype "passive"))
      (node (ref "R25") (pin "1") (pinfunction "1_1") (pintype "passive"))
    )
    (net (code "146") (name "Net-(C10-Pad1)") (class "Default")
      (node (ref "C10") (pin "1") (pinfunction "1_1") (pintype "passive"))
      (node (ref "R28") (pin "1") (pinfunction "1_1") (pintype "passive"))
    )
    (net (code "147") (name "Net-(C11-Pad1)") (class "Default")
      (node (ref "C11") (pin "1") (pinfunction "1_1") (pintype "passive"))
      (node (ref "R31") (pin "1") (pinfunction "1_1") (pintype "passive"))
    )
    (net (code "148") (name "Net-(C12-Pad1)") (class "Default")
      (node (ref "C12") (pin "1") (pinfunction "1_1") (pintype "passive"))
      (node (ref "R34") (pin "1") (pinfunction "1_1") (pintype "passive"))
    )
    (net (code "149") (name "Net-(C13-Pad1)") (class "Default")
      (node (ref "C13") (pin "1") (pinfunction "1_1") (pintype "passive"))
      (node (ref "R37") (pin "1") (pinfunction "1_1") (pintype "passive"))
    )
    (net (code "150") (name "Net-(C14-Pad1)") (class "Default")
      (node (ref "C14") (pin "1") (pinfunction "1_1") (pintype "passive"))
      (node (ref "R43") (pin "1") (pinfunction "1_1") (pintype "passive"))
    )
    (net (code "151") (name "Net-(C15-Pad1)") (class "Default")
      (node (ref "C15") (pin "1") (pinfunction "1_1") (pintype "passive"))
      (node (ref "R46") (pin "1") (pinfunction "1_1") (pintype "passive"))
    )
    (net (code "152") (name "Net-(C16-Pad1)") (class "Default")
      (node (ref "C16") (pin "1") (pinfunction "1_1") (pintype "passive"))
      (node (ref "R60") (pin "1") (pinfunction "1_1") (pintype "passive"))
      (node (ref "R61") (pin "2") (pinfunction "2_2") (pintype "passive"))
    )
    (net (code "153") (name "Net-(C20-Pad1)") (class "Default")
      (node (ref "C20") (pin "1") (pinfunction "1_1") (pintype "passive"))
      (node (ref "R40") (pin "1") (pinfunction "1_1") (pintype "passive"))
    )
    (net (code "154") (name "Net-(C41-Pad1)") (class "Default")
      (node (ref "C41") (pin "1") (pinfunction "1_1") (pintype "passive"))
      (node (ref "R88") (pin "1") (pinfunction "1_1") (pintype "passive"))
    )
    (net (code "155") (name "Net-(C42-Pad1)") (class "Default")
      (node (ref "C42") (pin "1") (pinfunction "1_1") (pintype "passive"))
      (node (ref "R89") (pin "1") (pinfunction "1_1") (pintype "passive"))
    )
    (net (code "156") (name "Net-(C43-Pad1)") (class "Default")
      (node (ref "C43") (pin "1") (pinfunction "1_1") (pintype "passive"))
      (node (ref "R90") (pin "1") (pinfunction "1_1") (pintype "passive"))
    )
    (net (code "157") (name "Net-(C44-Pad1)") (class "Default")
      (node (ref "C44") (pin "1") (pinfunction "1_1") (pintype "passive"))
      (node (ref "R91") (pin "1") (pinfunction "1_1") (pintype "passive"))
    )
    (net (code "158") (name "Net-(C45-Pad1)") (class "Default")
      (node (ref "C45") (pin "1") (pinfunction "1_1") (pintype "passive"))
      (node (ref "R92") (pin "1") (pinfunction "1_1") (pintype "passive"))
    )
    (net (code "159") (name "Net-(C46-Pad1)") (class "Default")
      (node (ref "C46") (pin "1") (pinfunction "1_1") (pintype "passive"))
      (node (ref "R93") (pin "1") (pinfunction "1_1") (pintype "passive"))
    )
    (net (code "160") (name "Net-(C47-Pad1)") (class "Default")
      (node (ref "C47") (pin "1") (pinfunction "1_1") (pintype "passive"))
      (node (ref "R94") (pin "1") (pinfunction "1_1") (pintype "passive"))
    )
    (net (code "161") (name "Net-(C48-Pad1)") (class "Default")
      (node (ref "C48") (pin "1") (pinfunction "1_1") (pintype "passive"))
      (node (ref "R95") (pin "1") (pinfunction "1_1") (pintype "passive"))
    )
    (net (code "162") (name "Net-(C49-Pad1)") (class "Default")
      (node (ref "C49") (pin "1") (pinfunction "1_1") (pintype "passive"))
      (node (ref "R96") (pin "1") (pinfunction "1_1") (pintype "passive"))
    )
    (net (code "163") (name "Net-(C50-Pad1)") (class "Default")
      (node (ref "C50") (pin "1") (pinfunction "1_1") (pintype "passive"))
      (node (ref "R97") (pin "1") (pinfunction "1_1") (pintype "passive"))
    )
    (net (code "164") (name "Net-(C51-Pad1)") (class "Default")
      (node (ref "C51") (pin "1") (pinfunction "1_1") (pintype "passive"))
      (node (ref "R98") (pin "1") (pinfunction "1_1") (pintype "passive"))
    )
    (net (code "165") (name "Net-(C52-Pad1)") (class "Default")
      (node (ref "C52") (pin "1") (pinfunction "1_1") (pintype "passive"))
      (node (ref "R99") (pin "1") (pinfunction "1_1") (pintype "passive"))
    )
    (net (code "166") (name "Net-(C53-Pad1)") (class "Default")
      (node (ref "C53") (pin "1") (pinfunction "1_1") (pintype "passive"))
      (node (ref "R100") (pin "1") (pinfunction "1_1") (pintype "passive"))
    )
    (net (code "167") (name "Net-(C54-Pad1)") (class "Default")
      (node (ref "C54") (pin "1") (pinfunction "1_1") (pintype "passive"))
      (node (ref "R101") (pin "1") (pinfunction "1_1") (pintype "passive"))
    )
    (net (code "168") (name "Net-(C55-Pad1)") (class "Default")
      (node (ref "C55") (pin "1") (pinfunction "1_1") (pintype "passive"))
      (node (ref "R102") (pin "1") (pinfunction "1_1") (pintype "passive"))
    )
    (net (code "169") (name "Net-(C56-Pad1)") (class "Default")
      (node (ref "C56") (pin "1") (pinfunction "1_1") (pintype "passive"))
      (node (ref "R103") (pin "1") (pinfunction "1_1") (pintype "passive"))
    )
    (net (code "170") (name "Net-(C57-Pad1)") (class "Default")
      (node (ref "C57") (pin "1") (pinfunction "1_1") (pintype "passive"))
      (node (ref "R104") (pin "1") (pinfunction "1_1") (pintype "passive"))
    )
    (net (code "171") (name "Net-(C58-Pad1)") (class "Default")
      (node (ref "C58") (pin "1") (pinfunction "1_1") (pintype "passive"))
      (node (ref "R105") (pin "1") (pinfunction "1_1") (pintype "passive"))
    )
    (net (code "172") (name "Net-(C59-Pad1)") (class "Default")
      (node (ref "C59") (pin "1") (pinfunction "1_1") (pintype "passive"))
      (node (ref "R106") (pin "1") (pinfunction "1_1") (pintype "passive"))
    )
    (net (code "173") (name "Net-(C60-Pad1)") (class "Default")
      (node (ref "C60") (pin "1") (pinfunction "1_1") (pintype "passive"))
      (node (ref "R107") (pin "1") (pinfunction "1_1") (pintype "passive"))
    )
    (net (code "174") (name "Net-(C61-Pad1)") (class "Default")
      (node (ref "C61") (pin "1") (pinfunction "1_1") (pintype "passive"))
      (node (ref "R108") (pin "1") (pinfunction "1_1") (pintype "passive"))
    )
    (net (code "175") (name "Net-(C62-Pad1)") (class "Default")
      (node (ref "C62") (pin "1") (pinfunction "1_1") (pintype "passive"))
      (node (ref "R109") (pin "1") (pinfunction "1_1") (pintype "passive"))
    )
    (net (code "176") (name "Net-(C63-Pad1)") (class "Default")
      (node (ref "C63") (pin "1") (pinfunction "1_1") (pintype "passive"))
      (node (ref "R110") (pin "1") (pinfunction "1_1") (pintype "passive"))
    )
    (net (code "177") (name "Net-(C64-Pad1)") (class "Default")
      (node (ref "C64") (pin "1") (pinfunction "1_1") (pintype "passive"))
      (node (ref "R111") (pin "1") (pinfunction "1_1") (pintype "passive"))
    )
    (net (code "178") (name "Net-(C65-Pad1)") (class "Default")
      (node (ref "C65") (pin "1") (pinfunction "1_1") (pintype "passive"))
      (node (ref "R112") (pin "1") (pinfunction "1_1") (pintype "passive"))
    )
    (net (code "179") (name "Net-(C66-Pad1)") (class "Default")
      (node (ref "C66") (pin "1") (pinfunction "1_1") (pintype "passive"))
      (node (ref "R113") (pin "1") (pinfunction "1_1") (pintype "passive"))
    )
    (net (code "180") (name "Net-(C67-Pad1)") (class "Default")
      (node (ref "C67") (pin "1") (pinfunction "1_1") (pintype "passive"))
      (node (ref "R114") (pin "1") (pinfunction "1_1") (pintype "passive"))
    )
    (net (code "181") (name "Net-(C68-Pad1)") (class "Default")
      (node (ref "C68") (pin "1") (pinfunction "1_1") (pintype "passive"))
      (node (ref "R115") (pin "1") (pinfunction "1_1") (pintype "passive"))
    )
    (net (code "182") (name "Net-(C69-Pad1)") (class "Default")
      (node (ref "C69") (pin "1") (pinfunction "1_1") (pintype "passive"))
      (node (ref "R116") (pin "1") (pinfunction "1_1") (pintype "passive"))
    )
    (net (code "183") (name "Net-(C70-Pad1)") (class "Default")
      (node (ref "C70") (pin "1") (pinfunction "1_1") (pintype "passive"))
      (node (ref "R117") (pin "1") (pinfunction "1_1") (pintype "passive"))
    )
    (net (code "184") (name "Net-(C71-Pad1)") (class "Default")
      (node (ref "C71") (pin "1") (pinfunction "1_1") (pintype "passive"))
      (node (ref "R118") (pin "1") (pinfunction "1_1") (pintype "passive"))
    )
    (net (code "185") (name "Net-(C72-Pad1)") (class "Default")
      (node (ref "C72") (pin "1") (pinfunction "1_1") (pintype "passive"))
      (node (ref "R119") (pin "1") (pinfunction "1_1") (pintype "passive"))
    )
    (net (code "186") (name "Net-(C73-Pad1)") (class "Default")
      (node (ref "C73") (pin "1") (pinfunction "1_1") (pintype "passive"))
      (node (ref "R120") (pin "1") (pinfunction "1_1") (pintype "passive"))
    )
    (net (code "187") (name "Net-(C74-Pad1)") (class "Default")
      (node (ref "C74") (pin "1") (pinfunction "1_1") (pintype "passive"))
      (node (ref "R121") (pin "1") (pinfunction "1_1") (pintype "passive"))
    )
    (net (code "188") (name "Net-(C75-Pad1)") (class "Default")
      (node (ref "C75") (pin "1") (pinfunction "1_1") (pintype "passive"))
      (node (ref "R122") (pin "1") (pinfunction "1_1") (pintype "passive"))
    )
    (net (code "189") (name "Net-(C76-Pad1)") (class "Default")
      (node (ref "C76") (pin "1") (pinfunction "1_1") (pintype "passive"))
      (node (ref "R123") (pin "1") (pinfunction "1_1") (pintype "passive"))
    )
    (net (code "190") (name "Net-(C77-Pad1)") (class "Default")
      (node (ref "C77") (pin "1") (pinfunction "1_1") (pintype "passive"))
      (node (ref "R124") (pin "1") (pinfunction "1_1") (pintype "passive"))
    )
    (net (code "191") (name "Net-(C78-Pad1)") (class "Default")
      (node (ref "C78") (pin "1") (pinfunction "1_1") (pintype "passive"))
      (node (ref "R125") (pin "1") (pinfunction "1_1") (pintype "passive"))
    )
    (net (code "192") (name "Net-(C79-Pad1)") (class "Default")
      (node (ref "C79") (pin "1") (pinfunction "1_1") (pintype "passive"))
      (node (ref "R126") (pin "1") (pinfunction "1_1") (pintype "passive"))
    )
    (net (code "193") (name "Net-(C80-Pad1)") (class "Default")
      (node (ref "C80") (pin "1") (pinfunction "1_1") (pintype "passive"))
      (node (ref "R127") (pin "1") (pinfunction "1_1") (pintype "passive"))
    )
    (net (code "194") (name "Net-(C81-Pad1)") (class "Default")
      (node (ref "C81") (pin "1") (pinfunction "1_1") (pintype "passive"))
      (node (ref "R128") (pin "1") (pinfunction "1_1") (pintype "passive"))
    )
    (net (code "195") (name "Net-(C82-Pad1)") (class "Default")
      (node (ref "C82") (pin "1") (pinfunction "1_1") (pintype "passive"))
      (node (ref "R129") (pin "1") (pinfunction "1_1") (pintype "passive"))
    )
    (net (code "196") (name "Net-(C83-Pad1)") (class "Default")
      (node (ref "C83") (pin "1") (pinfunction "1_1") (pintype "passive"))
      (node (ref "R130") (pin "1") (pinfunction "1_1") (pintype "passive"))
    )
    (net (code "197") (name "Net-(C84-Pad1)") (class "Default")
      (node (ref "C84") (pin "1") (pinfunction "1_1") (pintype "passive"))
      (node (ref "R131") (pin "1") (pinfunction "1_1") (pintype "passive"))
    )
    (net (code "198") (name "Net-(C85-Pad1)") (class "Default")
      (node (ref "C85") (pin "1") (pinfunction "1_1") (pintype "passive"))
      (node (ref "R132") (pin "1") (pinfunction "1_1") (pintype "passive"))
    )
    (net (code "199") (name "Net-(C86-Pad1)") (class "Default")
      (node (ref "C86") (pin "1") (pinfunction "1_1") (pintype "passive"))
      (node (ref "R133") (pin "1") (pinfunction "1_1") (pintype "passive"))
    )
    (net (code "200") (name "Net-(C87-Pad1)") (class "Default")
      (node (ref "C87") (pin "1") (pinfunction "1_1") (pintype "passive"))
      (node (ref "R134") (pin "1") (pinfunction "1_1") (pintype "passive"))
    )
    (net (code "201") (name "Net-(C88-Pad1)") (class "Default")
      (node (ref "C88") (pin "1") (pinfunction "1_1") (pintype "passive"))
      (node (ref "R135") (pin "1") (pinfunction "1_1") (pintype "passive"))
    )
    (net (code "202") (name "Net-(IC1-G2A)") (class "Default")
      (node (ref "IC1") (pin "4") (pinfunction "G2A_4") (pintype "input"))
      (node (ref "IC1") (pin "5") (pinfunction "G2B_5") (pintype "input"))
      (node (ref "R50") (pin "2") (pinfunction "2_2") (pintype "passive"))
    )
    (net (code "203") (name "Net-(IC2-G2A)") (class "Default")
      (node (ref "IC2") (pin "4") (pinfunction "G2A_4") (pintype "input"))
      (node (ref "IC2") (pin "5") (pinfunction "G2B_5") (pintype "input"))
      (node (ref "R53") (pin "2") (pinfunction "2_2") (pintype "passive"))
    )
    (net (code "204") (name "Net-(IC3-VBUS)") (class "Default")
      (node (ref "IC3") (pin "42") (pinfunction "VBUS_42") (pintype "bidirectional"))
      (node (ref "R58") (pin "2") (pinfunction "2_2") (pintype "passive"))
    )
    (net (code "205") (name "Net-(IC4-INH)") (class "Default")
      (node (ref "IC4") (pin "6") (pinfunction "INH_6") (pintype "input"))
      (node (ref "R51") (pin "2") (pinfunction "2_2") (pintype "passive"))
    )
    (net (code "206") (name "Net-(IC5-INH)") (class "Default")
      (node (ref "IC5") (pin "6") (pinfunction "INH_6") (pintype "input"))
      (node (ref "R54") (pin "2") (pinfunction "2_2") (pintype "passive"))
    )
    (net (code "207") (name "Net-(IC6-BYPASS)") (class "Default")
      (node (ref "C23") (pin "1") (pinfunction "1_1") (pintype "passive"))
      (node (ref "IC6") (pin "4") (pinfunction "BYPASS_4") (pintype "input"))
    )
    (net (code "208") (name "Net-(Q1-B)") (class "Default")
      (node (ref "Q1") (pin "1") (pinfunction "B_1") (pintype "passive"))
      (node (ref "R2") (pin "2") (pinfunction "2_2") (pintype "passive"))
      (node (ref "R3") (pin "2") (pinfunction "2_2") (pintype "passive"))
    )
    (net (code "209") (name "Net-(Q2-B)") (class "Default")
      (node (ref "Q2") (pin "1") (pinfunction "B_1") (pintype "passive"))
      (node (ref "R41") (pin "2") (pinfunction "2_2") (pintype "passive"))
      (node (ref "R42") (pin "2") (pinfunction "2_2") (pintype "passive"))
    )
    (net (code "210") (name "Net-(Q3-B)") (class "Default")
      (node (ref "Q3") (pin "1") (pinfunction "B_1") (pintype "passive"))
      (node (ref "R5") (pin "2") (pinfunction "2_2") (pintype "passive"))
      (node (ref "R6") (pin "2") (pinfunction "2_2") (pintype "passive"))
    )
    (net (code "211") (name "Net-(Q4-B)") (class "Default")
      (node (ref "Q4") (pin "1") (pinfunction "B_1") (pintype "passive"))
      (node (ref "R8") (pin "2") (pinfunction "2_2") (pintype "passive"))
      (node (ref "R9") (pin "2") (pinfunction "2_2") (pintype "passive"))
    )
    (net (code "212") (name "Net-(Q5-B)") (class "Default")
      (node (ref "Q5") (pin "1") (pinfunction "B_1") (pintype "passive"))
      (node (ref "R11") (pin "2") (pinfunction "2_2") (pintype "passive"))
      (node (ref "R12") (pin "2") (pinfunction "2_2") (pintype "passive"))
    )
    (net (code "213") (name "Net-(Q6-B)") (class "Default")
      (node (ref "Q6") (pin "1") (pinfunction "B_1") (pintype "passive"))
      (node (ref "R14") (pin "2") (pinfunction "2_2") (pintype "passive"))
      (node (ref "R15") (pin "2") (pinfunction "2_2") (pintype "passive"))
    )
    (net (code "214") (name "Net-(Q7-B)") (class "Default")
      (node (ref "Q7") (pin "1") (pinfunction "B_1") (pintype "passive"))
      (node (ref "R17") (pin "2") (pinfunction "2_2") (pintype "passive"))
      (node (ref "R18") (pin "2") (pinfunction "2_2") (pintype "passive"))
    )
    (net (code "215") (name "Net-(Q8-B)") (class "Default")
      (node (ref "Q8") (pin "1") (pinfunction "B_1") (pintype "passive"))
      (node (ref "R20") (pin "2") (pinfunction "2_2") (pintype "passive"))
      (node (ref "R21") (pin "2") (pinfunction "2_2") (pintype "passive"))
    )
    (net (code "216") (name "Net-(Q9-B)") (class "Default")
      (node (ref "Q9") (pin "1") (pinfunction "B_1") (pintype "passive"))
      (node (ref "R23") (pin "2") (pinfunction "2_2") (pintype "passive"))
      (node (ref "R24") (pin "2") (pinfunction "2_2") (pintype "passive"))
    )
    (net (code "217") (name "Net-(Q10-B)") (class "Default")
      (node (ref "Q10") (pin "1") (pinfunction "B_1") (pintype "passive"))
      (node (ref "R26") (pin "2") (pinfunction "2_2") (pintype "passive"))
      (node (ref "R27") (pin "2") (pinfunction "2_2") (pintype "passive"))
    )
    (net (code "218") (name "Net-(Q11-B)") (class "Default")
      (node (ref "Q11") (pin "1") (pinfunction "B_1") (pintype "passive"))
      (node (ref "R29") (pin "2") (pinfunction "2_2") (pintype "passive"))
      (node (ref "R30") (pin "2") (pinfunction "2_2") (pintype "passive"))
    )
    (net (code "219") (name "Net-(Q12-B)") (class "Default")
      (node (ref "Q12") (pin "1") (pinfunction "B_1") (pintype "passive"))
      (node (ref "R32") (pin "2") (pinfunction "2_2") (pintype "passive"))
      (node (ref "R33") (pin "2") (pinfunction "2_2") (pintype "passive"))
    )
    (net (code "220") (name "Net-(Q13-B)") (class "Default")
      (node (ref "Q13") (pin "1") (pinfunction "B_1") (pintype "passive"))
      (node (ref "R35") (pin "2") (pinfunction "2_2") (pintype "passive"))
      (node (ref "R36") (pin "2") (pinfunction "2_2") (pintype "passive"))
    )
    (net (code "221") (name "Net-(Q14-B)") (class "Default")
      (node (ref "Q14") (pin "1") (pinfunction "B_1") (pintype "passive"))
      (node (ref "R38") (pin "2") (pinfunction "2_2") (pintype "passive"))
      (node (ref "R39") (pin "2") (pinfunction "2_2") (pintype "passive"))
    )
    (net (code "222") (name "Net-(Q15-B)") (class "Default")
      (node (ref "Q15") (pin "1") (pinfunction "B_1") (pintype "passive"))
      (node (ref "R44") (pin "2") (pinfunction "2_2") (pintype "passive"))
      (node (ref "R45") (pin "2") (pinfunction "2_2") (pintype "passive"))
    )
    (net (code "223") (name "Net-(Q16-B)") (class "Default")
      (node (ref "Q16") (pin "1") (pinfunction "B_1") (pintype "passive"))
      (node (ref "R47") (pin "2") (pinfunction "2_2") (pintype "passive"))
      (node (ref "R48") (pin "2") (pinfunction "2_2") (pintype "passive"))
    )
    (net (code "224") (name "Net-(Q17-PadB)") (class "Default")
      (node (ref "Q17") (pin "B") (pinfunction "B_B") (pintype "passive"))
      (node (ref "R87") (pin "2") (pinfunction "2_2") (pintype "passive"))
    )
    (net (code "225") (name "Net-(R85-Pad1)") (class "Default")
      (node (ref "R85") (pin "1") (pinfunction "1_1") (pintype "passive"))
      (node (ref "R86") (pin "2") (pinfunction "2_2") (pintype "passive"))
    )
    (net (code "226") (name "Net-(SG1-2)") (class "Default")
      (node (ref "Q17") (pin "C") (pinfunction "C_C") (pintype "passive"))
      (node (ref "SG1") (pin "-") (pinfunction "2_-") (pintype "passive"))
    )
    (net (code "227") (name "Net-(TCH0A-KL)") (class "Default")
      (node (ref "R62") (pin "2") (pinfunction "2_2") (pintype "passive"))
      (node (ref "TCH0") (pin "1") (pinfunction "KL_1") (pintype "passive"))
    )
    (net (code "228") (name "Net-(TCH0B-KL)") (class "Default")
      (node (ref "R71") (pin "2") (pinfunction "2_2") (pintype "passive"))
      (node (ref "TCH0") (pin "10") (pinfunction "KL_10") (pintype "passive"))
    )
    (net (code "229") (name "Net-(TCH0C-KL)") (class "Default")
      (node (ref "R72") (pin "2") (pinfunction "2_2") (pintype "passive"))
      (node (ref "TCH0") (pin "11") (pinfunction "KL_11") (pintype "passive"))
    )
    (net (code "230") (name "Net-(TCH0D-KL)") (class "Default")
      (node (ref "R63") (pin "2") (pinfunction "2_2") (pintype "passive"))
      (node (ref "TCH0") (pin "2") (pinfunction "KL_2") (pintype "passive"))
    )
    (net (code "231") (name "Net-(TCH0E-KL)") (class "Default")
      (node (ref "R64") (pin "2") (pinfunction "2_2") (pintype "passive"))
      (node (ref "TCH0") (pin "3") (pinfunction "KL_3") (pintype "passive"))
    )
    (net (code "232") (name "Net-(TCH0F-KL)") (class "Default")
      (node (ref "R65") (pin "2") (pinfunction "2_2") (pintype "passive"))
      (node (ref "TCH0") (pin "4") (pinfunction "KL_4") (pintype "passive"))
    )
    (net (code "233") (name "Net-(TCH0G-KL)") (class "Default")
      (node (ref "R66") (pin "2") (pinfunction "2_2") (pintype "passive"))
      (node (ref "TCH0") (pin "5") (pinfunction "KL_5") (pintype "passive"))
    )
    (net (code "234") (name "Net-(TCH0H-KL)") (class "Default")
      (node (ref "R67") (pin "2") (pinfunction "2_2") (pintype "passive"))
      (node (ref "TCH0") (pin "6") (pinfunction "KL_6") (pintype "passive"))
    )
    (net (code "235") (name "Net-(TCH0I-KL)") (class "Default")
      (node (ref "R68") (pin "2") (pinfunction "2_2") (pintype "passive"))
      (node (ref "TCH0") (pin "7") (pinfunction "KL_7") (pintype "passive"))
    )
    (net (code "236") (name "Net-(TCH0J-KL)") (class "Default")
      (node (ref "R69") (pin "2") (pinfunction "2_2") (pintype "passive"))
      (node (ref "TCH0") (pin "8") (pinfunction "KL_8") (pintype "passive"))
    )
    (net (code "237") (name "Net-(TCH0K-KL)") (class "Default")
      (node (ref "R70") (pin "2") (pinfunction "2_2") (pintype "passive"))
      (node (ref "TCH0") (pin "9") (pinfunction "KL_9") (pintype "passive"))
    )
    (net (code "238") (name "Net-(TCH1A-KL)") (class "Default")
      (node (ref "R73") (pin "2") (pinfunction "2_2") (pintype "passive"))
      (node (ref "TCH1") (pin "1") (pinfunction "KL_1") (pintype "passive"))
    )
    (net (code "239") (name "Net-(TCH1B-KL)") (class "Default")
      (node (ref "R82") (pin "2") (pinfunction "2_2") (pintype "passive"))
      (node (ref "TCH1") (pin "10") (pinfunction "KL_10") (pintype "passive"))
    )
    (net (code "240") (name "Net-(TCH1C-KL)") (class "Default")
      (node (ref "R83") (pin "2") (pinfunction "2_2") (pintype "passive"))
      (node (ref "TCH1") (pin "11") (pinfunction "KL_11") (pintype "passive"))
    )
    (net (code "241") (name "Net-(TCH1D-KL)") (class "Default")
      (node (ref "R74") (pin "2") (pinfunction "2_2") (pintype "passive"))
      (node (ref "TCH1") (pin "2") (pinfunction "KL_2") (pintype "passive"))
    )
    (net (code "242") (name "Net-(TCH1E-KL)") (class "Default")
      (node (ref "R75") (pin "2") (pinfunction "2_2") (pintype "passive"))
      (node (ref "TCH1") (pin "3") (pinfunction "KL_3") (pintype "passive"))
    )
    (net (code "243") (name "Net-(TCH1F-KL)") (class "Default")
      (node (ref "R76") (pin "2") (pinfunction "2_2") (pintype "passive"))
      (node (ref "TCH1") (pin "4") (pinfunction "KL_4") (pintype "passive"))
    )
    (net (code "244") (name "Net-(TCH1G-KL)") (class "Default")
      (node (ref "R77") (pin "2") (pinfunction "2_2") (pintype "passive"))
      (node (ref "TCH1") (pin "5") (pinfunction "KL_5") (pintype "passive"))
    )
    (net (code "245") (name "Net-(TCH1H-KL)") (class "Default")
      (node (ref "R78") (pin "2") (pinfunction "2_2") (pintype "passive"))
      (node (ref "TCH1") (pin "6") (pinfunction "KL_6") (pintype "passive"))
    )
    (net (code "246") (name "Net-(TCH1I-KL)") (class "Default")
      (node (ref "R79") (pin "2") (pinfunction "2_2") (pintype "passive"))
      (node (ref "TCH1") (pin "7") (pinfunction "KL_7") (pintype "passive"))
    )
    (net (code "247") (name "Net-(TCH1J-KL)") (class "Default")
      (node (ref "R80") (pin "2") (pinfunction "2_2") (pintype "passive"))
      (node (ref "TCH1") (pin "8") (pinfunction "KL_8") (pintype "passive"))
    )
    (net (code "248") (name "Net-(TCH1K-KL)") (class "Default")
      (node (ref "R81") (pin "2") (pinfunction "2_2") (pintype "passive"))
      (node (ref "TCH1") (pin "9") (pinfunction "KL_9") (pintype "passive"))
    )
    (net (code "249") (name "Net-(U$1-IREF)") (class "Default")
      (node (ref "R55") (pin "2") (pinfunction "2_2") (pintype "passive"))
      (node (ref "U$1") (pin "32") (pinfunction "IREF_32") (pintype "input"))
    )
    (net (code "250") (name "Net-(U$2-IREF)") (class "Default")
      (node (ref "R56") (pin "2") (pinfunction "2_2") (pintype "passive"))
      (node (ref "U$2") (pin "32") (pinfunction "IREF_32") (pintype "input"))
    )
    (net (code "251") (name "V+") (class "Default")
      (node (ref "C35") (pin "+") (pinfunction "+_+") (pintype "passive"))
      (node (ref "IC7") (pin "3") (pinfunction "IN_3") (pintype "input"))
      (node (ref "J1") (pin "1") (pinfunction "1_1") (pintype "passive"))
      (node (ref "R84") (pin "1") (pinfunction "1_1") (pintype "passive"))
    )
    (net (code "252") (name "unconnected-(X1-Pad4)") (class "Default")
      (node (ref "X1") (pin "4") (pinfunction "4_4") (pintype "passive"))
    )
  )
)
